# untitled.net
KiCad netlist of a schematic drawn in EAGLE
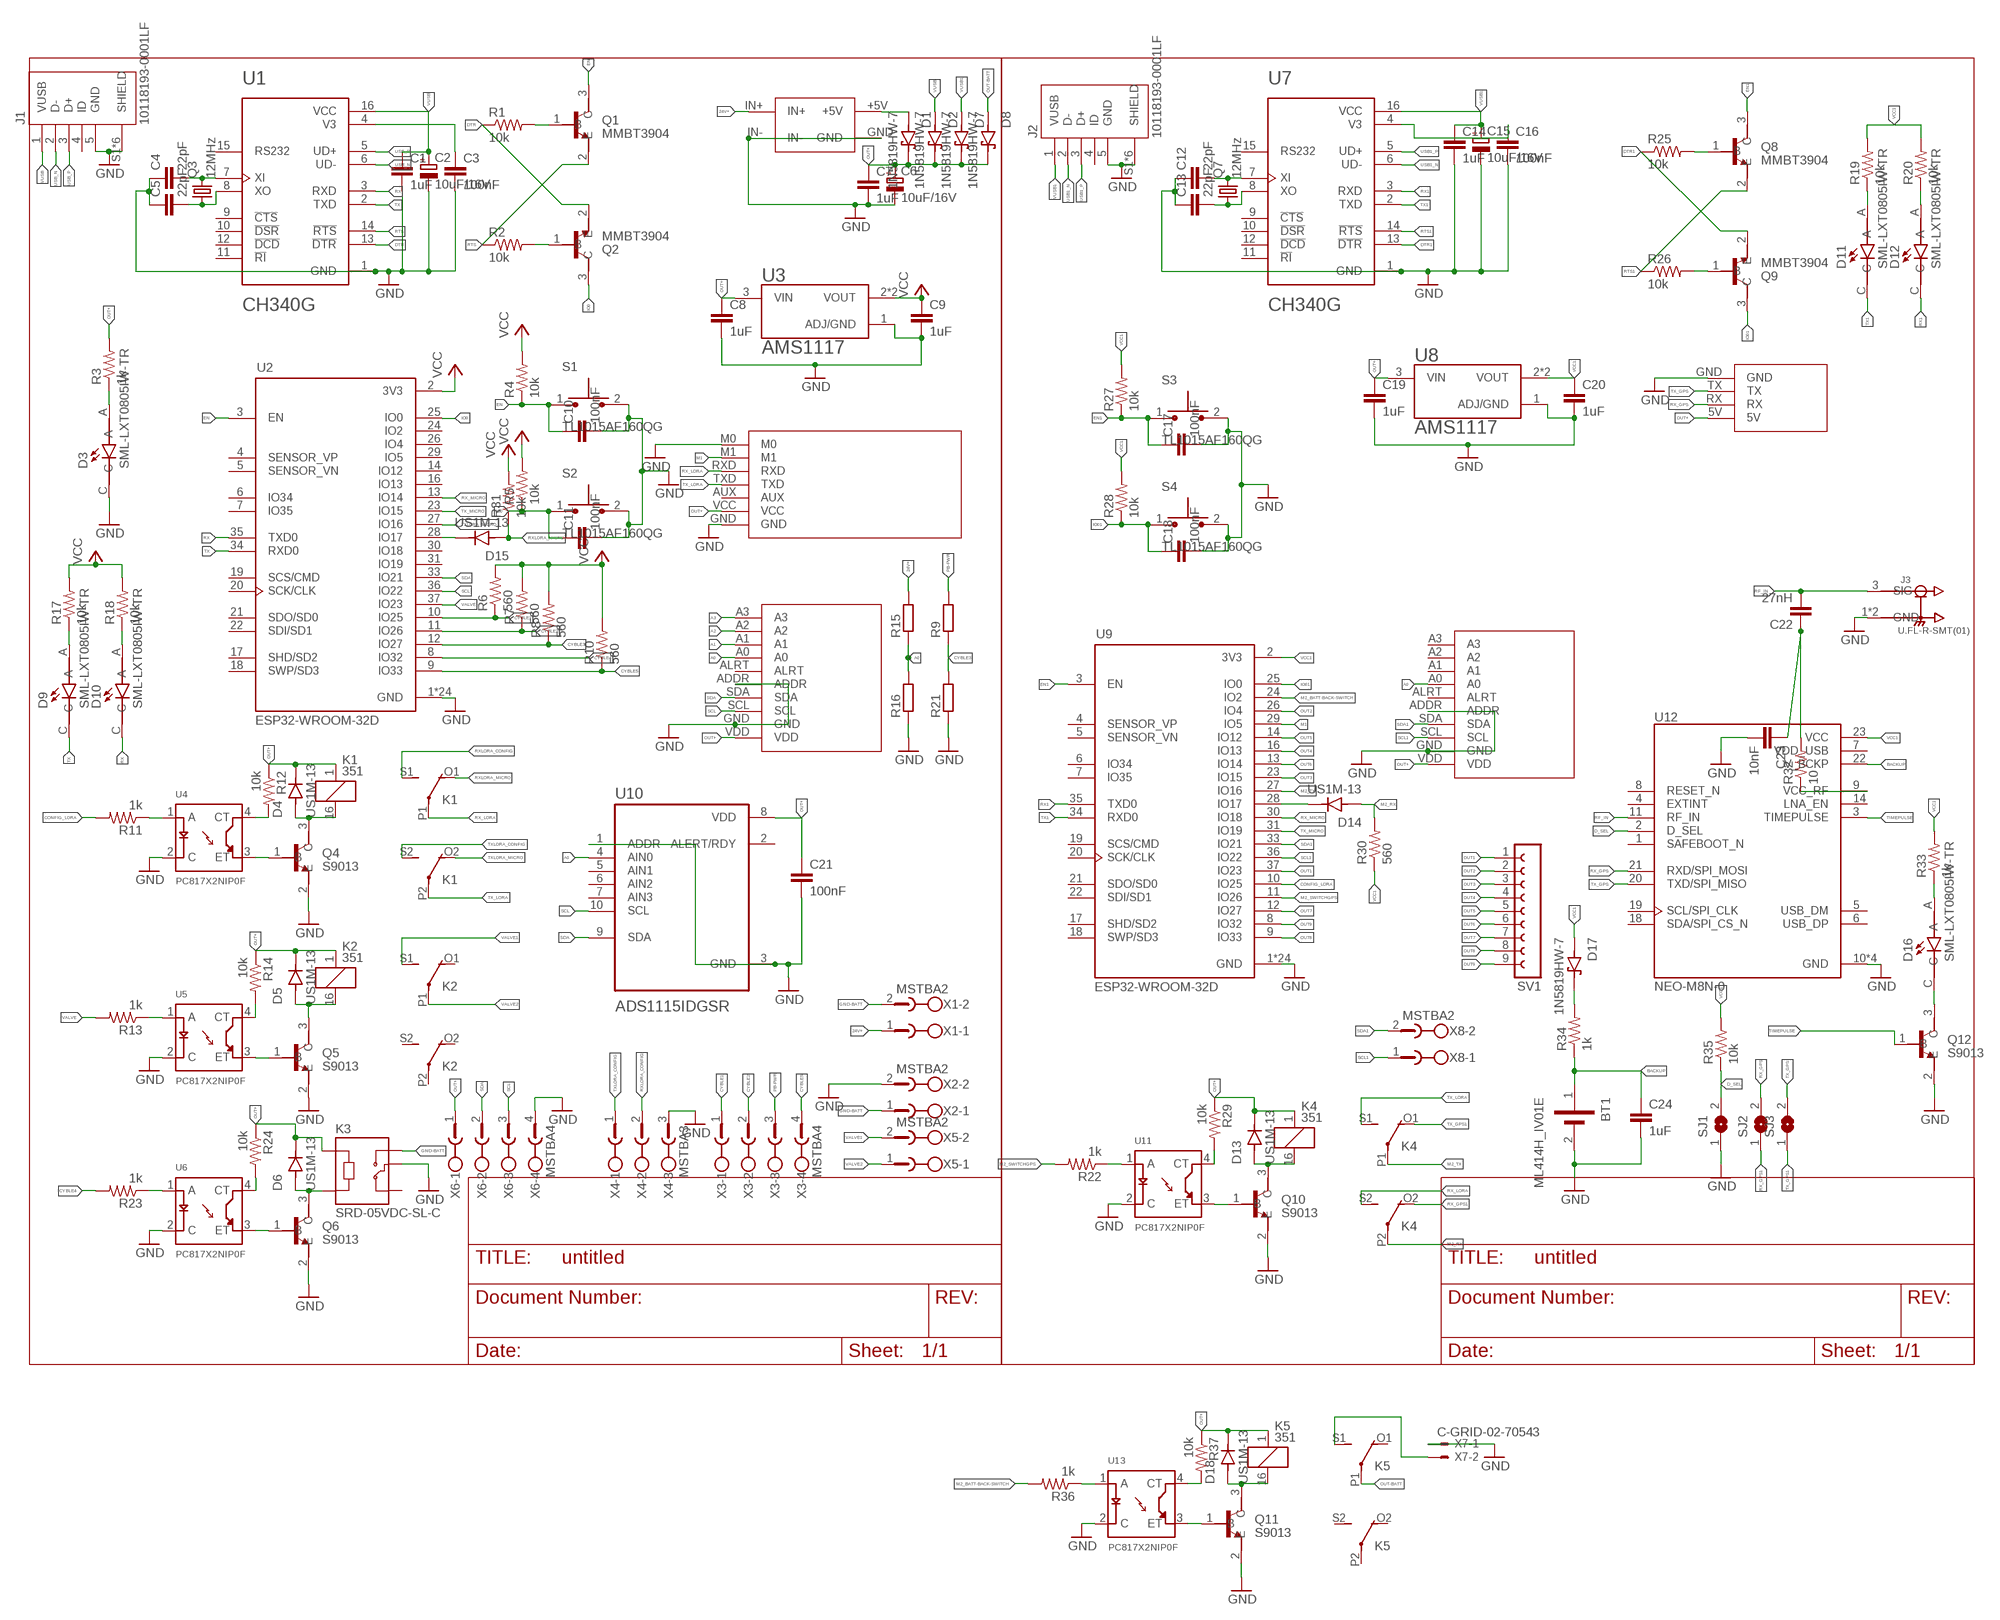
[diagram p0: schematic, sheet 1]

(export (version "E")
  (design (tool "Eeschema 10.0.6"))
  (components
    (comp (ref "ADS1")
      (value "ADS1115")
      (footprint "eagle-import:ADS1115")
      (libsource (lib "eagle-import") (part "ADS1115"))
    )
    (comp (ref "ADS2")
      (value "ADS1115")
      (footprint "eagle-import:ADS1115")
      (libsource (lib "eagle-import") (part "ADS1115"))
    )
    (comp (ref "BT1")
      (value "ML414H_IV01E")
      (footprint "eagle-import:SEIKO_ML414H_IV01E")
      (fields (field (name "MF") "Seiko Instruments") (field (name "MP") "ML414H IV01E"))
      (libsource (lib "eagle-import") (part "ML414H_IV01E"))
    )
    (comp (ref "C1")
      (value "1uF")
      (footprint "eagle-import:C0805K")
      (libsource (lib "eagle-import") (part "C-EUC0805K"))
    )
    (comp (ref "C2")
      (value "10uF/16V")
      (footprint "eagle-import:153CLV-0505")
      (libsource (lib "eagle-import") (part "CPOL-EU153CLV-0505"))
    )
    (comp (ref "C3")
      (value "100nF")
      (footprint "eagle-import:C0805K")
      (libsource (lib "eagle-import") (part "C-EUC0805K"))
    )
    (comp (ref "C4")
      (value "22pF")
      (footprint "eagle-import:C0805K")
      (libsource (lib "eagle-import") (part "C-EUC0805K"))
    )
    (comp (ref "C5")
      (value "22pF")
      (footprint "eagle-import:C0805K")
      (libsource (lib "eagle-import") (part "C-EUC0805K"))
    )
    (comp (ref "C6")
      (value "10uF/16V")
      (footprint "eagle-import:153CLV-0505")
      (libsource (lib "eagle-import") (part "CPOL-EU153CLV-0505"))
    )
    (comp (ref "C7")
      (value "1uF")
      (footprint "eagle-import:C0805K")
      (libsource (lib "eagle-import") (part "C-EUC0805K"))
    )
    (comp (ref "C8")
      (value "1uF")
      (footprint "eagle-import:C0805K")
      (libsource (lib "eagle-import") (part "C-EUC0805K"))
    )
    (comp (ref "C9")
      (value "1uF")
      (footprint "eagle-import:C0805K")
      (libsource (lib "eagle-import") (part "C-EUC0805K"))
    )
    (comp (ref "C10")
      (value "100nF")
      (footprint "eagle-import:C0805K")
      (libsource (lib "eagle-import") (part "C-EUC0805K"))
    )
    (comp (ref "C11")
      (value "100nF")
      (footprint "eagle-import:C0805K")
      (libsource (lib "eagle-import") (part "C-EUC0805K"))
    )
    (comp (ref "C12")
      (value "22pF")
      (footprint "eagle-import:C0805K")
      (libsource (lib "eagle-import") (part "C-EUC0805K"))
    )
    (comp (ref "C13")
      (value "22pF")
      (footprint "eagle-import:C0805K")
      (libsource (lib "eagle-import") (part "C-EUC0805K"))
    )
    (comp (ref "C14")
      (value "1uF")
      (footprint "eagle-import:C0805K")
      (libsource (lib "eagle-import") (part "C-EUC0805K"))
    )
    (comp (ref "C15")
      (value "10uF/16V")
      (footprint "eagle-import:153CLV-0505")
      (libsource (lib "eagle-import") (part "CPOL-EU153CLV-0505"))
    )
    (comp (ref "C16")
      (value "100nF")
      (footprint "eagle-import:C0805K")
      (libsource (lib "eagle-import") (part "C-EUC0805K"))
    )
    (comp (ref "C17")
      (value "100nF")
      (footprint "eagle-import:C0805K")
      (libsource (lib "eagle-import") (part "C-EUC0805K"))
    )
    (comp (ref "C18")
      (value "100nF")
      (footprint "eagle-import:C0805K")
      (libsource (lib "eagle-import") (part "C-EUC0805K"))
    )
    (comp (ref "C19")
      (value "1uF")
      (footprint "eagle-import:C0805K")
      (libsource (lib "eagle-import") (part "C-EUC0805K"))
    )
    (comp (ref "C20")
      (value "1uF")
      (footprint "eagle-import:C0805K")
      (libsource (lib "eagle-import") (part "C-EUC0805K"))
    )
    (comp (ref "C21")
      (value "100nF")
      (footprint "eagle-import:C0805K")
      (libsource (lib "eagle-import") (part "C-EUC0805K"))
    )
    (comp (ref "C22")
      (value "27nH")
      (footprint "eagle-import:C0805K")
      (libsource (lib "eagle-import") (part "C-EUC0805K"))
    )
    (comp (ref "C23")
      (value "10nF")
      (footprint "eagle-import:C0805K")
      (libsource (lib "eagle-import") (part "C-EUC0805K"))
    )
    (comp (ref "C24")
      (value "1uF")
      (footprint "eagle-import:C0805K")
      (libsource (lib "eagle-import") (part "C-EUC0805K"))
    )
    (comp (ref "D1")
      (value "1N5819HW-7")
      (footprint "eagle-import:SOD3715X145N")
      (fields (field (name "MF") "Diodes Inc."))
      (libsource (lib "eagle-import") (part "1N5819HW-7"))
    )
    (comp (ref "D2")
      (value "1N5819HW-7")
      (footprint "eagle-import:SOD3715X145N")
      (fields (field (name "MF") "Diodes Inc."))
      (libsource (lib "eagle-import") (part "1N5819HW-7"))
    )
    (comp (ref "D3")
      (value "SML-LXT0805IW-TR")
      (footprint "eagle-import:LEDC2012X120N")
      (fields (field (name "MF") "Lumex Opto/Components"))
      (libsource (lib "eagle-import") (part "SML-LXT0805IW-TR"))
    )
    (comp (ref "D4")
      (value "US1M-13")
      (footprint "eagle-import:DIOM5226X240N")
      (fields (field (name "MF") "Diodes Incorporated"))
      (libsource (lib "eagle-import") (part "US1M-13"))
    )
    (comp (ref "D5")
      (value "US1M-13")
      (footprint "eagle-import:DIOM5226X240N")
      (fields (field (name "MF") "Diodes Incorporated"))
      (libsource (lib "eagle-import") (part "US1M-13"))
    )
    (comp (ref "D6")
      (value "US1M-13")
      (footprint "eagle-import:DIOM5226X240N")
      (fields (field (name "MF") "Diodes Incorporated"))
      (libsource (lib "eagle-import") (part "US1M-13"))
    )
    (comp (ref "D7")
      (value "1N5819HW-7")
      (footprint "eagle-import:SOD3715X145N")
      (fields (field (name "MF") "Diodes Inc."))
      (libsource (lib "eagle-import") (part "1N5819HW-7"))
    )
    (comp (ref "D8")
      (value "1N5819HW-7")
      (footprint "eagle-import:SOD3715X145N")
      (fields (field (name "MF") "Diodes Inc."))
      (libsource (lib "eagle-import") (part "1N5819HW-7"))
    )
    (comp (ref "D9")
      (value "SML-LXT0805IW-TR")
      (footprint "eagle-import:LEDC2012X120N")
      (fields (field (name "MF") "Lumex Opto/Components"))
      (libsource (lib "eagle-import") (part "SML-LXT0805IW-TR"))
    )
    (comp (ref "D10")
      (value "SML-LXT0805IW-TR")
      (footprint "eagle-import:LEDC2012X120N")
      (fields (field (name "MF") "Lumex Opto/Components"))
      (libsource (lib "eagle-import") (part "SML-LXT0805IW-TR"))
    )
    (comp (ref "D11")
      (value "SML-LXT0805IW-TR")
      (footprint "eagle-import:LEDC2012X120N")
      (fields (field (name "MF") "Lumex Opto/Components"))
      (libsource (lib "eagle-import") (part "SML-LXT0805IW-TR"))
    )
    (comp (ref "D12")
      (value "SML-LXT0805IW-TR")
      (footprint "eagle-import:LEDC2012X120N")
      (fields (field (name "MF") "Lumex Opto/Components"))
      (libsource (lib "eagle-import") (part "SML-LXT0805IW-TR"))
    )
    (comp (ref "D13")
      (value "US1M-13")
      (footprint "eagle-import:DIOM5226X240N")
      (fields (field (name "MF") "Diodes Incorporated"))
      (libsource (lib "eagle-import") (part "US1M-13"))
    )
    (comp (ref "D14")
      (value "US1M-13")
      (footprint "eagle-import:DIOM5226X240N")
      (fields (field (name "MF") "Diodes Incorporated"))
      (libsource (lib "eagle-import") (part "US1M-13"))
    )
    (comp (ref "D15")
      (value "US1M-13")
      (footprint "eagle-import:DIOM5226X240N")
      (fields (field (name "MF") "Diodes Incorporated"))
      (libsource (lib "eagle-import") (part "US1M-13"))
    )
    (comp (ref "D16")
      (value "SML-LXT0805IW-TR")
      (footprint "eagle-import:LEDC2012X120N")
      (fields (field (name "MF") "Lumex Opto/Components"))
      (libsource (lib "eagle-import") (part "SML-LXT0805IW-TR"))
    )
    (comp (ref "D17")
      (value "1N5819HW-7")
      (footprint "eagle-import:SOD3715X145N")
      (fields (field (name "MF") "Diodes Inc."))
      (libsource (lib "eagle-import") (part "1N5819HW-7"))
    )
    (comp (ref "D18")
      (value "US1M-13")
      (footprint "eagle-import:DIOM5226X240N")
      (fields (field (name "MF") "Diodes Incorporated"))
      (libsource (lib "eagle-import") (part "US1M-13"))
    )
    (comp (ref "EBYTEE220-900T22D1")
      (value "EBYTEE220-900T22D")
      (footprint "eagle-import:EBYTEE220-900T22D")
      (libsource (lib "eagle-import") (part "EBYTEE220-900T22D"))
    )
    (comp (ref "J1")
      (value "10118193-0001LF")
      (footprint "eagle-import:FCI_10118193-0001LF")
      (fields (field (name "MF") "FCI"))
      (libsource (lib "eagle-import") (part "10118193-0001LF"))
    )
    (comp (ref "J2")
      (value "10118193-0001LF")
      (footprint "eagle-import:FCI_10118193-0001LF")
      (fields (field (name "MF") "FCI"))
      (libsource (lib "eagle-import") (part "10118193-0001LF"))
    )
    (comp (ref "J3")
      (value "U.FL-R-SMT(01)")
      (footprint "eagle-import:HRS_U.FL-R-SMT(01)")
      (fields (field (name "MF") "Hirose"))
      (libsource (lib "eagle-import") (part "U.FL-R-SMT(01)"))
    )
    (comp (ref "K1")
      (value "351")
      (footprint "eagle-import:351")
      (libsource (lib "eagle-import") (part "351"))
    )
    (comp (ref "K2")
      (value "351")
      (footprint "eagle-import:351")
      (libsource (lib "eagle-import") (part "351"))
    )
    (comp (ref "K3")
      (value "SRD-05VDC-SL-C")
      (footprint "eagle-import:RELAY_SRD-05VDC-SL-C")
      (fields (field (name "MF") "Songle Relay"))
      (libsource (lib "eagle-import") (part "SRD-05VDC-SL-C"))
    )
    (comp (ref "K4")
      (value "351")
      (footprint "eagle-import:351")
      (libsource (lib "eagle-import") (part "351"))
    )
    (comp (ref "K5")
      (value "351")
      (footprint "eagle-import:351")
      (libsource (lib "eagle-import") (part "351"))
    )
    (comp (ref "NEO-6MGPS1")
      (value "NEO-6MGPS")
      (footprint "eagle-import:NEO-6MGPS")
      (libsource (lib "eagle-import") (part "NEO-6MGPS"))
    )
    (comp (ref "Q1")
      (value "MMBT3904")
      (footprint "eagle-import:SOT95P240X120-3N")
      (fields (field (name "MF") "ON Semiconductor"))
      (libsource (lib "eagle-import") (part "MMBT3904"))
    )
    (comp (ref "Q2")
      (value "MMBT3904")
      (footprint "eagle-import:SOT95P240X120-3N")
      (fields (field (name "MF") "ON Semiconductor"))
      (libsource (lib "eagle-import") (part "MMBT3904"))
    )
    (comp (ref "Q3")
      (value "12MHz")
      (footprint "eagle-import:SM49")
      (libsource (lib "eagle-import") (part "CRYSTALSM49"))
    )
    (comp (ref "Q4")
      (value "S9013")
      (footprint "eagle-import:SOT95P240X120-3N")
      (fields (field (name "MF") "JCET"))
      (libsource (lib "eagle-import") (part "S9013"))
    )
    (comp (ref "Q5")
      (value "S9013")
      (footprint "eagle-import:SOT95P240X120-3N")
      (fields (field (name "MF") "JCET"))
      (libsource (lib "eagle-import") (part "S9013"))
    )
    (comp (ref "Q6")
      (value "S9013")
      (footprint "eagle-import:SOT95P240X120-3N")
      (fields (field (name "MF") "JCET"))
      (libsource (lib "eagle-import") (part "S9013"))
    )
    (comp (ref "Q7")
      (value "12MHz")
      (footprint "eagle-import:SM49")
      (libsource (lib "eagle-import") (part "CRYSTALSM49"))
    )
    (comp (ref "Q8")
      (value "MMBT3904")
      (footprint "eagle-import:SOT95P240X120-3N")
      (fields (field (name "MF") "ON Semiconductor"))
      (libsource (lib "eagle-import") (part "MMBT3904"))
    )
    (comp (ref "Q9")
      (value "MMBT3904")
      (footprint "eagle-import:SOT95P240X120-3N")
      (fields (field (name "MF") "ON Semiconductor"))
      (libsource (lib "eagle-import") (part "MMBT3904"))
    )
    (comp (ref "Q10")
      (value "S9013")
      (footprint "eagle-import:SOT95P240X120-3N")
      (fields (field (name "MF") "JCET"))
      (libsource (lib "eagle-import") (part "S9013"))
    )
    (comp (ref "Q11")
      (value "S9013")
      (footprint "eagle-import:SOT95P240X120-3N")
      (fields (field (name "MF") "JCET"))
      (libsource (lib "eagle-import") (part "S9013"))
    )
    (comp (ref "Q12")
      (value "S9013")
      (footprint "eagle-import:SOT95P240X120-3N")
      (fields (field (name "MF") "JCET"))
      (libsource (lib "eagle-import") (part "S9013"))
    )
    (comp (ref "R1")
      (value "10k")
      (footprint "eagle-import:M0805")
      (libsource (lib "eagle-import") (part "R-US_M0805"))
    )
    (comp (ref "R2")
      (value "10k")
      (footprint "eagle-import:M0805")
      (libsource (lib "eagle-import") (part "R-US_M0805"))
    )
    (comp (ref "R3")
      (value "1k")
      (footprint "eagle-import:M0805")
      (libsource (lib "eagle-import") (part "R-US_M0805"))
    )
    (comp (ref "R4")
      (value "10k")
      (footprint "eagle-import:M0805")
      (libsource (lib "eagle-import") (part "R-US_M0805"))
    )
    (comp (ref "R5")
      (value "10k")
      (footprint "eagle-import:M0805")
      (libsource (lib "eagle-import") (part "R-US_M0805"))
    )
    (comp (ref "R6")
      (value "560")
      (footprint "eagle-import:M0805")
      (libsource (lib "eagle-import") (part "R-US_M0805"))
    )
    (comp (ref "R7")
      (value "560")
      (footprint "eagle-import:M0805")
      (libsource (lib "eagle-import") (part "R-US_M0805"))
    )
    (comp (ref "R8")
      (value "560")
      (footprint "eagle-import:M0805")
      (libsource (lib "eagle-import") (part "R-US_M0805"))
    )
    (comp (ref "R9")
      (value "R-EU_0207/12")
      (footprint "eagle-import:0207_12")
      (libsource (lib "eagle-import") (part "R-EU_0207/12"))
    )
    (comp (ref "R10")
      (value "560")
      (footprint "eagle-import:M0805")
      (libsource (lib "eagle-import") (part "R-US_M0805"))
    )
    (comp (ref "R11")
      (value "1k")
      (footprint "eagle-import:M0805")
      (libsource (lib "eagle-import") (part "R-US_M0805"))
    )
    (comp (ref "R12")
      (value "10k")
      (footprint "eagle-import:M0805")
      (libsource (lib "eagle-import") (part "R-US_M0805"))
    )
    (comp (ref "R13")
      (value "1k")
      (footprint "eagle-import:M0805")
      (libsource (lib "eagle-import") (part "R-US_M0805"))
    )
    (comp (ref "R14")
      (value "10k")
      (footprint "eagle-import:M0805")
      (libsource (lib "eagle-import") (part "R-US_M0805"))
    )
    (comp (ref "R15")
      (value "R-EU_0207/12")
      (footprint "eagle-import:0207_12")
      (libsource (lib "eagle-import") (part "R-EU_0207/12"))
    )
    (comp (ref "R16")
      (value "R-EU_0207/12")
      (footprint "eagle-import:0207_12")
      (libsource (lib "eagle-import") (part "R-EU_0207/12"))
    )
    (comp (ref "R17")
      (value "10k")
      (footprint "eagle-import:M0805")
      (libsource (lib "eagle-import") (part "R-US_M0805"))
    )
    (comp (ref "R18")
      (value "10k")
      (footprint "eagle-import:M0805")
      (libsource (lib "eagle-import") (part "R-US_M0805"))
    )
    (comp (ref "R19")
      (value "10k")
      (footprint "eagle-import:M0805")
      (libsource (lib "eagle-import") (part "R-US_M0805"))
    )
    (comp (ref "R20")
      (value "10k")
      (footprint "eagle-import:M0805")
      (libsource (lib "eagle-import") (part "R-US_M0805"))
    )
    (comp (ref "R21")
      (value "R-EU_0207/12")
      (footprint "eagle-import:0207_12")
      (libsource (lib "eagle-import") (part "R-EU_0207/12"))
    )
    (comp (ref "R22")
      (value "1k")
      (footprint "eagle-import:M0805")
      (libsource (lib "eagle-import") (part "R-US_M0805"))
    )
    (comp (ref "R23")
      (value "1k")
      (footprint "eagle-import:M0805")
      (libsource (lib "eagle-import") (part "R-US_M0805"))
    )
    (comp (ref "R24")
      (value "10k")
      (footprint "eagle-import:M0805")
      (libsource (lib "eagle-import") (part "R-US_M0805"))
    )
    (comp (ref "R25")
      (value "10k")
      (footprint "eagle-import:M0805")
      (libsource (lib "eagle-import") (part "R-US_M0805"))
    )
    (comp (ref "R26")
      (value "10k")
      (footprint "eagle-import:M0805")
      (libsource (lib "eagle-import") (part "R-US_M0805"))
    )
    (comp (ref "R27")
      (value "10k")
      (footprint "eagle-import:M0805")
      (libsource (lib "eagle-import") (part "R-US_M0805"))
    )
    (comp (ref "R28")
      (value "10k")
      (footprint "eagle-import:M0805")
      (libsource (lib "eagle-import") (part "R-US_M0805"))
    )
    (comp (ref "R29")
      (value "10k")
      (footprint "eagle-import:M0805")
      (libsource (lib "eagle-import") (part "R-US_M0805"))
    )
    (comp (ref "R30")
      (value "560")
      (footprint "eagle-import:M0805")
      (libsource (lib "eagle-import") (part "R-US_M0805"))
    )
    (comp (ref "R31")
      (value "10k")
      (footprint "eagle-import:M0805")
      (libsource (lib "eagle-import") (part "R-US_M0805"))
    )
    (comp (ref "R32")
      (value "10")
      (footprint "eagle-import:M0805")
      (libsource (lib "eagle-import") (part "R-US_M0805"))
    )
    (comp (ref "R33")
      (value "1k")
      (footprint "eagle-import:M0805")
      (libsource (lib "eagle-import") (part "R-US_M0805"))
    )
    (comp (ref "R34")
      (value "1k")
      (footprint "eagle-import:M0805")
      (libsource (lib "eagle-import") (part "R-US_M0805"))
    )
    (comp (ref "R35")
      (value "10k")
      (footprint "eagle-import:M0805")
      (libsource (lib "eagle-import") (part "R-US_M0805"))
    )
    (comp (ref "R36")
      (value "1k")
      (footprint "eagle-import:M0805")
      (libsource (lib "eagle-import") (part "R-US_M0805"))
    )
    (comp (ref "R37")
      (value "10k")
      (footprint "eagle-import:M0805")
      (libsource (lib "eagle-import") (part "R-US_M0805"))
    )
    (comp (ref "S1")
      (value "TL1015AF160QG")
      (footprint "eagle-import:SW_TL1015AF160QG")
      (fields (field (name "MF") "E-Switch"))
      (libsource (lib "eagle-import") (part "TL1015AF160QG"))
    )
    (comp (ref "S2")
      (value "TL1015AF160QG")
      (footprint "eagle-import:SW_TL1015AF160QG")
      (fields (field (name "MF") "E-Switch"))
      (libsource (lib "eagle-import") (part "TL1015AF160QG"))
    )
    (comp (ref "S3")
      (value "TL1015AF160QG")
      (footprint "eagle-import:SW_TL1015AF160QG")
      (fields (field (name "MF") "E-Switch"))
      (libsource (lib "eagle-import") (part "TL1015AF160QG"))
    )
    (comp (ref "S4")
      (value "TL1015AF160QG")
      (footprint "eagle-import:SW_TL1015AF160QG")
      (fields (field (name "MF") "E-Switch"))
      (libsource (lib "eagle-import") (part "TL1015AF160QG"))
    )
    (comp (ref "SJ1") (value "SJ") (footprint "eagle-import:SJ") (libsource (lib "eagle-import") (part "SJ")))
    (comp (ref "SJ2") (value "SJ") (footprint "eagle-import:SJ") (libsource (lib "eagle-import") (part "SJ")))
    (comp (ref "SJ3") (value "SJ") (footprint "eagle-import:SJ") (libsource (lib "eagle-import") (part "SJ")))
    (comp (ref "SUPER-STEPDOWN1")
      (value "SUPER-STEPDOWN")
      (footprint "eagle-import:SUPER-STEPDOWN")
      (libsource (lib "eagle-import") (part "SUPER-STEPDOWN"))
    )
    (comp (ref "SV1")
      (value "FE09-1")
      (footprint "eagle-import:FE09")
      (libsource (lib "eagle-import") (part "FE09-1"))
    )
    (comp (ref "U1")
      (value "CH340G")
      (footprint "eagle-import:SOIC127P600X180-16N")
      (fields (field (name "MF") "WCH") (field (name "MP") "Ch340G"))
      (libsource (lib "eagle-import") (part "CH340G"))
    )
    (comp (ref "U2")
      (value "ESP32-WROOM-32D")
      (footprint "eagle-import:MODULE_ESP32-WROOM-32D")
      (fields (field (name "MF") "Espressif Systems"))
      (libsource (lib "eagle-import") (part "ESP32-WROOM-32D"))
    )
    (comp (ref "U3")
      (value "AMS1117")
      (footprint "eagle-import:SOT229P700X180-4N")
      (fields (field (name "MF") "Advanced Monolithic Systems"))
      (libsource (lib "eagle-import") (part "AMS1117"))
    )
    (comp (ref "U4")
      (value "PC817X2NIP0F")
      (footprint "eagle-import:SOT254P975X400-4N")
      (fields (field (name "MF") "Sharp Microelectronics"))
      (libsource (lib "eagle-import") (part "PC817X2NIP0F"))
    )
    (comp (ref "U5")
      (value "PC817X2NIP0F")
      (footprint "eagle-import:SOT254P975X400-4N")
      (fields (field (name "MF") "Sharp Microelectronics"))
      (libsource (lib "eagle-import") (part "PC817X2NIP0F"))
    )
    (comp (ref "U6")
      (value "PC817X2NIP0F")
      (footprint "eagle-import:SOT254P975X400-4N")
      (fields (field (name "MF") "Sharp Microelectronics"))
      (libsource (lib "eagle-import") (part "PC817X2NIP0F"))
    )
    (comp (ref "U7")
      (value "CH340G")
      (footprint "eagle-import:SOIC127P600X180-16N")
      (fields (field (name "MF") "WCH") (field (name "MP") "Ch340G"))
      (libsource (lib "eagle-import") (part "CH340G"))
    )
    (comp (ref "U8")
      (value "AMS1117")
      (footprint "eagle-import:SOT229P700X180-4N")
      (fields (field (name "MF") "Advanced Monolithic Systems"))
      (libsource (lib "eagle-import") (part "AMS1117"))
    )
    (comp (ref "U9")
      (value "ESP32-WROOM-32D")
      (footprint "eagle-import:MODULE_ESP32-WROOM-32D")
      (fields (field (name "MF") "Espressif Systems"))
      (libsource (lib "eagle-import") (part "ESP32-WROOM-32D"))
    )
    (comp (ref "U10")
      (value "ADS1115IDGSR")
      (footprint "eagle-import:SOP50P490X110-10N")
      (fields (field (name "MF") "Texas Instruments"))
      (libsource (lib "eagle-import") (part "ADS1115IDGSR"))
    )
    (comp (ref "U11")
      (value "PC817X2NIP0F")
      (footprint "eagle-import:SOT254P975X400-4N")
      (fields (field (name "MF") "Sharp Microelectronics"))
      (libsource (lib "eagle-import") (part "PC817X2NIP0F"))
    )
    (comp (ref "U12")
      (value "NEO-M8N-0")
      (footprint "eagle-import:XCVR_NEO-M8N-0")
      (fields (field (name "MF") "U-Blox America"))
      (libsource (lib "eagle-import") (part "NEO-M8N-0"))
    )
    (comp (ref "U13")
      (value "PC817X2NIP0F")
      (footprint "eagle-import:SOT254P975X400-4N")
      (fields (field (name "MF") "Sharp Microelectronics"))
      (libsource (lib "eagle-import") (part "PC817X2NIP0F"))
    )
    (comp (ref "X1")
      (value "MSTBA2")
      (footprint "eagle-import:MSTBA2")
      (fields (field (name "MF") "FARNELL") (field (name "MPN") "1757242"))
      (libsource (lib "eagle-import") (part "MSTBA2"))
    )
    (comp (ref "X2")
      (value "MSTBA2")
      (footprint "eagle-import:MSTBA2")
      (fields (field (name "MF") "FARNELL") (field (name "MPN") "1757242"))
      (libsource (lib "eagle-import") (part "MSTBA2"))
    )
    (comp (ref "X3")
      (value "MSTBA4")
      (footprint "eagle-import:MSTBA4")
      (fields (field (name "MF") "FARNELL") (field (name "MPN") "1757268"))
      (libsource (lib "eagle-import") (part "MSTBA4"))
    )
    (comp (ref "X4")
      (value "MSTBA3")
      (footprint "eagle-import:MSTBA3")
      (fields (field (name "MF") "FARNELL") (field (name "MPN") "1757255"))
      (libsource (lib "eagle-import") (part "MSTBA3"))
    )
    (comp (ref "X5")
      (value "MSTBA2")
      (footprint "eagle-import:MSTBA2")
      (fields (field (name "MF") "FARNELL") (field (name "MPN") "1757242"))
      (libsource (lib "eagle-import") (part "MSTBA2"))
    )
    (comp (ref "X6")
      (value "MSTBA4")
      (footprint "eagle-import:MSTBA4")
      (fields (field (name "MF") "FARNELL") (field (name "MPN") "1757268"))
      (libsource (lib "eagle-import") (part "MSTBA4"))
    )
    (comp (ref "X7")
      (value "C-GRID-02-70543")
      (footprint "eagle-import:70543-02")
      (fields (field (name "MF") "MOLEX"))
      (libsource (lib "eagle-import") (part "C-GRID-02-70543"))
    )
    (comp (ref "X8")
      (value "MSTBA2")
      (footprint "eagle-import:MSTBA2")
      (fields (field (name "MF") "FARNELL") (field (name "MPN") "1757242"))
      (libsource (lib "eagle-import") (part "MSTBA2"))
    )
  )
  (nets
    (net (code "1") (name "/VDD_USB") (class "Default")
      (node (ref "U12") (pin "7") (pinfunction "VDD_USB_7") (pintype "power_in"))
    )
    (net (code "2") (name "24V+") (class "Default")
      (node (ref "R15") (pin "2") (pinfunction "2_2") (pintype "passive"))
      (node (ref "SUPER-STEPDOWN1") (pin "IN+") (pinfunction "IN+_IN+") (pintype "bidirectional"))
      (node (ref "X1") (pin "1") (pinfunction "1_1") (pintype "passive"))
    )
    (net (code "3") (name "A0") (class "Default")
      (node (ref "ADS1") (pin "A0") (pinfunction "A0_A0") (pintype "bidirectional"))
      (node (ref "ADS2") (pin "A0") (pinfunction "A0_A0") (pintype "bidirectional"))
      (node (ref "R15") (pin "1") (pinfunction "1_1") (pintype "passive"))
      (node (ref "R16") (pin "2") (pinfunction "2_2") (pintype "passive"))
      (node (ref "U10") (pin "4") (pinfunction "AIN0_4") (pintype "input"))
    )
    (net (code "4") (name "A1") (class "Default")
      (node (ref "ADS1") (pin "A1") (pinfunction "A1_A1") (pintype "bidirectional"))
    )
    (net (code "5") (name "A2") (class "Default")
      (node (ref "ADS1") (pin "A2") (pinfunction "A2_A2") (pintype "bidirectional"))
    )
    (net (code "6") (name "A3") (class "Default")
      (node (ref "ADS1") (pin "A3") (pinfunction "A3_A3") (pintype "bidirectional"))
    )
    (net (code "7") (name "BACKUP") (class "Default")
      (node (ref "BT1") (pin "1") (pinfunction "POS_1") (pintype "passive"))
      (node (ref "C24") (pin "1") (pinfunction "1_1") (pintype "passive"))
      (node (ref "R34") (pin "1") (pinfunction "1_1") (pintype "passive"))
      (node (ref "U12") (pin "22") (pinfunction "V_BCKP_22") (pintype "power_in"))
    )
    (net (code "8") (name "CONFIG_LORA") (class "Default")
      (node (ref "R11") (pin "2") (pinfunction "2_2") (pintype "passive"))
      (node (ref "U9") (pin "10") (pinfunction "IO25_10") (pintype "bidirectional"))
    )
    (net (code "9") (name "CYBLE1") (class "Default")
      (node (ref "R6") (pin "1") (pinfunction "1_1") (pintype "passive"))
      (node (ref "U2") (pin "10") (pinfunction "IO25_10") (pintype "bidirectional"))
      (node (ref "X3") (pin "1") (pinfunction "1_1") (pintype "passive"))
    )
    (net (code "10") (name "CYBLE2") (class "Default")
      (node (ref "R7") (pin "1") (pinfunction "1_1") (pintype "passive"))
      (node (ref "U2") (pin "11") (pinfunction "IO26_11") (pintype "bidirectional"))
      (node (ref "X3") (pin "2") (pinfunction "1_2") (pintype "passive"))
    )
    (net (code "11") (name "CYBLE3") (class "Default")
      (node (ref "R21") (pin "2") (pinfunction "2_2") (pintype "passive"))
      (node (ref "R8") (pin "1") (pinfunction "1_1") (pintype "passive"))
      (node (ref "R9") (pin "1") (pinfunction "1_1") (pintype "passive"))
      (node (ref "U2") (pin "12") (pinfunction "IO27_12") (pintype "bidirectional"))
    )
    (net (code "12") (name "CYBLE4") (class "Default")
      (node (ref "R23") (pin "2") (pinfunction "2_2") (pintype "passive"))
      (node (ref "U2") (pin "8") (pinfunction "IO32_8") (pintype "bidirectional"))
    )
    (net (code "13") (name "CYBLE5") (class "Default")
      (node (ref "R10") (pin "1") (pinfunction "1_1") (pintype "passive"))
      (node (ref "U2") (pin "9") (pinfunction "IO33_9") (pintype "bidirectional"))
      (node (ref "X3") (pin "4") (pinfunction "1_4") (pintype "passive"))
    )
    (net (code "14") (name "DTR") (class "Default")
      (node (ref "Q2") (pin "2") (pinfunction "E_2") (pintype "passive"))
      (node (ref "R1") (pin "1") (pinfunction "1_1") (pintype "passive"))
      (node (ref "U1") (pin "13") (pinfunction "~{DTR}_13") (pintype "output"))
    )
    (net (code "15") (name "DTR1") (class "Default")
      (node (ref "Q9") (pin "2") (pinfunction "E_2") (pintype "passive"))
      (node (ref "R25") (pin "1") (pinfunction "1_1") (pintype "passive"))
      (node (ref "U7") (pin "13") (pinfunction "~{DTR}_13") (pintype "output"))
    )
    (net (code "16") (name "D_SEL") (class "Default")
      (node (ref "R35") (pin "1") (pinfunction "1_1") (pintype "passive"))
      (node (ref "SJ1") (pin "2") (pinfunction "2_2") (pintype "passive"))
      (node (ref "U12") (pin "2") (pinfunction "D_SEL_2") (pintype "input"))
    )
    (net (code "17") (name "EN") (class "Default")
      (node (ref "C10") (pin "1") (pinfunction "1_1") (pintype "passive"))
      (node (ref "Q1") (pin "3") (pinfunction "C_3") (pintype "passive"))
      (node (ref "R4") (pin "1") (pinfunction "1_1") (pintype "passive"))
      (node (ref "S1") (pin "1") (pinfunction "1_1") (pintype "passive"))
      (node (ref "U2") (pin "3") (pinfunction "EN_3") (pintype "input"))
    )
    (net (code "18") (name "EN1") (class "Default")
      (node (ref "C17") (pin "1") (pinfunction "1_1") (pintype "passive"))
      (node (ref "Q8") (pin "3") (pinfunction "C_3") (pintype "passive"))
      (node (ref "R27") (pin "1") (pinfunction "1_1") (pintype "passive"))
      (node (ref "S3") (pin "1") (pinfunction "1_1") (pintype "passive"))
      (node (ref "U9") (pin "3") (pinfunction "EN_3") (pintype "input"))
    )
    (net (code "19") (name "GND") (class "Default")
      (node (ref "ADS1") (pin "ADDR") (pinfunction "ADDR_ADDR") (pintype "bidirectional"))
      (node (ref "ADS1") (pin "GND") (pinfunction "GND_GND") (pintype "bidirectional"))
      (node (ref "ADS2") (pin "ADDR") (pinfunction "ADDR_ADDR") (pintype "bidirectional"))
      (node (ref "ADS2") (pin "GND") (pinfunction "GND_GND") (pintype "bidirectional"))
      (node (ref "BT1") (pin "2") (pinfunction "NEG_2") (pintype "passive"))
      (node (ref "C1") (pin "2") (pinfunction "2_2") (pintype "passive"))
      (node (ref "C10") (pin "2") (pinfunction "2_2") (pintype "passive"))
      (node (ref "C11") (pin "2") (pinfunction "2_2") (pintype "passive"))
      (node (ref "C12") (pin "1") (pinfunction "1_1") (pintype "passive"))
      (node (ref "C13") (pin "1") (pinfunction "1_1") (pintype "passive"))
      (node (ref "C14") (pin "2") (pinfunction "2_2") (pintype "passive"))
      (node (ref "C15") (pin "-") (pinfunction "-_-") (pintype "passive"))
      (node (ref "C16") (pin "2") (pinfunction "2_2") (pintype "passive"))
      (node (ref "C17") (pin "2") (pinfunction "2_2") (pintype "passive"))
      (node (ref "C18") (pin "2") (pinfunction "2_2") (pintype "passive"))
      (node (ref "C19") (pin "2") (pinfunction "2_2") (pintype "passive"))
      (node (ref "C2") (pin "-") (pinfunction "-_-") (pintype "passive"))
      (node (ref "C20") (pin "2") (pinfunction "2_2") (pintype "passive"))
      (node (ref "C21") (pin "2") (pinfunction "2_2") (pintype "passive"))
      (node (ref "C23") (pin "2") (pinfunction "2_2") (pintype "passive"))
      (node (ref "C24") (pin "2") (pinfunction "2_2") (pintype "passive"))
      (node (ref "C3") (pin "2") (pinfunction "2_2") (pintype "passive"))
      (node (ref "C4") (pin "1") (pinfunction "1_1") (pintype "passive"))
      (node (ref "C5") (pin "1") (pinfunction "1_1") (pintype "passive"))
      (node (ref "C6") (pin "-") (pinfunction "-_-") (pintype "passive"))
      (node (ref "C7") (pin "2") (pinfunction "2_2") (pintype "passive"))
      (node (ref "C8") (pin "2") (pinfunction "2_2") (pintype "passive"))
      (node (ref "C9") (pin "2") (pinfunction "2_2") (pintype "passive"))
      (node (ref "D3") (pin "C") (pinfunction "C_C") (pintype "passive"))
      (node (ref "EBYTEE220-900T22D1") (pin "GND") (pinfunction "GND_GND") (pintype "bidirectional"))
      (node (ref "EBYTEE220-900T22D1") (pin "M0") (pinfunction "M0_M0") (pintype "bidirectional"))
      (node (ref "J1") (pin "5") (pinfunction "GND_5") (pintype "passive"))
      (node (ref "J1") (pin "S1") (pinfunction "SHIELD_S1") (pintype "passive"))
      (node (ref "J1") (pin "S2") (pinfunction "SHIELD_S2") (pintype "passive"))
      (node (ref "J1") (pin "S3") (pinfunction "SHIELD_S3") (pintype "passive"))
      (node (ref "J1") (pin "S4") (pinfunction "SHIELD_S4") (pintype "passive"))
      (node (ref "J1") (pin "S5") (pinfunction "SHIELD_S5") (pintype "passive"))
      (node (ref "J1") (pin "S6") (pinfunction "SHIELD_S6") (pintype "passive"))
      (node (ref "J2") (pin "5") (pinfunction "GND_5") (pintype "passive"))
      (node (ref "J2") (pin "S1") (pinfunction "SHIELD_S1") (pintype "passive"))
      (node (ref "J2") (pin "S2") (pinfunction "SHIELD_S2") (pintype "passive"))
      (node (ref "J2") (pin "S3") (pinfunction "SHIELD_S3") (pintype "passive"))
      (node (ref "J2") (pin "S4") (pinfunction "SHIELD_S4") (pintype "passive"))
      (node (ref "J2") (pin "S5") (pinfunction "SHIELD_S5") (pintype "passive"))
      (node (ref "J2") (pin "S6") (pinfunction "SHIELD_S6") (pintype "passive"))
      (node (ref "J3") (pin "1") (pinfunction "GND_1") (pintype "passive"))
      (node (ref "J3") (pin "2") (pinfunction "GND_2") (pintype "passive"))
      (node (ref "K3") (pin "COM") (pinfunction "COM_COM") (pintype "passive"))
      (node (ref "NEO-6MGPS1") (pin "GND") (pinfunction "GND_GND") (pintype "bidirectional"))
      (node (ref "Q10") (pin "2") (pinfunction "E_2") (pintype "passive"))
      (node (ref "Q11") (pin "2") (pinfunction "E_2") (pintype "passive"))
      (node (ref "Q12") (pin "2") (pinfunction "E_2") (pintype "passive"))
      (node (ref "Q4") (pin "2") (pinfunction "E_2") (pintype "passive"))
      (node (ref "Q5") (pin "2") (pinfunction "E_2") (pintype "passive"))
      (node (ref "Q6") (pin "2") (pinfunction "E_2") (pintype "passive"))
      (node (ref "R16") (pin "1") (pinfunction "1_1") (pintype "passive"))
      (node (ref "R21") (pin "1") (pinfunction "1_1") (pintype "passive"))
      (node (ref "S1") (pin "2") (pinfunction "2_2") (pintype "passive"))
      (node (ref "S2") (pin "2") (pinfunction "2_2") (pintype "passive"))
      (node (ref "S3") (pin "2") (pinfunction "2_2") (pintype "passive"))
      (node (ref "S4") (pin "2") (pinfunction "2_2") (pintype "passive"))
      (node (ref "SJ1") (pin "1") (pinfunction "1_1") (pintype "passive"))
      (node (ref "SUPER-STEPDOWN1") (pin "GND") (pinfunction "GND_GND") (pintype "bidirectional"))
      (node (ref "SUPER-STEPDOWN1") (pin "IN-") (pinfunction "IN-_IN-") (pintype "bidirectional"))
      (node (ref "U1") (pin "1") (pinfunction "GND_1") (pintype "power_in"))
      (node (ref "U10") (pin "1") (pinfunction "ADDR_1") (pintype "input"))
      (node (ref "U10") (pin "3") (pinfunction "GND_3") (pintype "power_in"))
      (node (ref "U11") (pin "2") (pinfunction "C_2") (pintype "passive"))
      (node (ref "U12") (pin "10") (pinfunction "GND_10") (pintype "power_in"))
      (node (ref "U12") (pin "12") (pinfunction "GND_12") (pintype "power_in"))
      (node (ref "U12") (pin "13") (pinfunction "GND_13") (pintype "power_in"))
      (node (ref "U12") (pin "24") (pinfunction "GND_24") (pintype "power_in"))
      (node (ref "U13") (pin "2") (pinfunction "C_2") (pintype "passive"))
      (node (ref "U2") (pin "1") (pinfunction "GND_1") (pintype "power_in"))
      (node (ref "U2") (pin "15") (pinfunction "GND_15") (pintype "power_in"))
      (node (ref "U2") (pin "38") (pinfunction "GND_38") (pintype "power_in"))
      (node (ref "U2") (pin "39_1") (pinfunction "GND_39_1") (pintype "power_in"))
      (node (ref "U2") (pin "39_10") (pinfunction "GND_39_10") (pintype "power_in"))
      (node (ref "U2") (pin "39_11") (pinfunction "GND_39_11") (pintype "power_in"))
      (node (ref "U2") (pin "39_12") (pinfunction "GND_39_12") (pintype "power_in"))
      (node (ref "U2") (pin "39_13") (pinfunction "GND_39_13") (pintype "power_in"))
      (node (ref "U2") (pin "39_14") (pinfunction "GND_39_14") (pintype "power_in"))
      (node (ref "U2") (pin "39_15") (pinfunction "GND_39_15") (pintype "power_in"))
      (node (ref "U2") (pin "39_16") (pinfunction "GND_39_16") (pintype "power_in"))
      (node (ref "U2") (pin "39_17") (pinfunction "GND_39_17") (pintype "power_in"))
      (node (ref "U2") (pin "39_18") (pinfunction "GND_39_18") (pintype "power_in"))
      (node (ref "U2") (pin "39_19") (pinfunction "GND_39_19") (pintype "power_in"))
      (node (ref "U2") (pin "39_2") (pinfunction "GND_39_2") (pintype "power_in"))
      (node (ref "U2") (pin "39_20") (pinfunction "GND_39_20") (pintype "power_in"))
      (node (ref "U2") (pin "39_21") (pinfunction "GND_39_21") (pintype "power_in"))
      (node (ref "U2") (pin "39_3") (pinfunction "GND_39_3") (pintype "power_in"))
      (node (ref "U2") (pin "39_4") (pinfunction "GND_39_4") (pintype "power_in"))
      (node (ref "U2") (pin "39_5") (pinfunction "GND_39_5") (pintype "power_in"))
      (node (ref "U2") (pin "39_6") (pinfunction "GND_39_6") (pintype "power_in"))
      (node (ref "U2") (pin "39_7") (pinfunction "GND_39_7") (pintype "power_in"))
      (node (ref "U2") (pin "39_8") (pinfunction "GND_39_8") (pintype "power_in"))
      (node (ref "U2") (pin "39_9") (pinfunction "GND_39_9") (pintype "power_in"))
      (node (ref "U3") (pin "1") (pinfunction "ADJ/GND_1") (pintype "power_in"))
      (node (ref "U4") (pin "2") (pinfunction "C_2") (pintype "passive"))
      (node (ref "U5") (pin "2") (pinfunction "C_2") (pintype "passive"))
      (node (ref "U6") (pin "2") (pinfunction "C_2") (pintype "passive"))
      (node (ref "U7") (pin "1") (pinfunction "GND_1") (pintype "power_in"))
      (node (ref "U8") (pin "1") (pinfunction "ADJ/GND_1") (pintype "power_in"))
      (node (ref "U9") (pin "1") (pinfunction "GND_1") (pintype "power_in"))
      (node (ref "U9") (pin "15") (pinfunction "GND_15") (pintype "power_in"))
      (node (ref "U9") (pin "38") (pinfunction "GND_38") (pintype "power_in"))
      (node (ref "U9") (pin "39_1") (pinfunction "GND_39_1") (pintype "power_in"))
      (node (ref "U9") (pin "39_10") (pinfunction "GND_39_10") (pintype "power_in"))
      (node (ref "U9") (pin "39_11") (pinfunction "GND_39_11") (pintype "power_in"))
      (node (ref "U9") (pin "39_12") (pinfunction "GND_39_12") (pintype "power_in"))
      (node (ref "U9") (pin "39_13") (pinfunction "GND_39_13") (pintype "power_in"))
      (node (ref "U9") (pin "39_14") (pinfunction "GND_39_14") (pintype "power_in"))
      (node (ref "U9") (pin "39_15") (pinfunction "GND_39_15") (pintype "power_in"))
      (node (ref "U9") (pin "39_16") (pinfunction "GND_39_16") (pintype "power_in"))
      (node (ref "U9") (pin "39_17") (pinfunction "GND_39_17") (pintype "power_in"))
      (node (ref "U9") (pin "39_18") (pinfunction "GND_39_18") (pintype "power_in"))
      (node (ref "U9") (pin "39_19") (pinfunction "GND_39_19") (pintype "power_in"))
      (node (ref "U9") (pin "39_2") (pinfunction "GND_39_2") (pintype "power_in"))
      (node (ref "U9") (pin "39_20") (pinfunction "GND_39_20") (pintype "power_in"))
      (node (ref "U9") (pin "39_21") (pinfunction "GND_39_21") (pintype "power_in"))
      (node (ref "U9") (pin "39_3") (pinfunction "GND_39_3") (pintype "power_in"))
      (node (ref "U9") (pin "39_4") (pinfunction "GND_39_4") (pintype "power_in"))
      (node (ref "U9") (pin "39_5") (pinfunction "GND_39_5") (pintype "power_in"))
      (node (ref "U9") (pin "39_6") (pinfunction "GND_39_6") (pintype "power_in"))
      (node (ref "U9") (pin "39_7") (pinfunction "GND_39_7") (pintype "power_in"))
      (node (ref "U9") (pin "39_8") (pinfunction "GND_39_8") (pintype "power_in"))
      (node (ref "U9") (pin "39_9") (pinfunction "GND_39_9") (pintype "power_in"))
      (node (ref "X2") (pin "2") (pinfunction "1_2") (pintype "passive"))
      (node (ref "X4") (pin "3") (pinfunction "1_3") (pintype "passive"))
      (node (ref "X6") (pin "4") (pinfunction "1_4") (pintype "passive"))
      (node (ref "X7") (pin "1") (pinfunction "S_1") (pintype "passive"))
    )
    (net (code "20") (name "GND-BATT") (class "Default")
      (node (ref "K3") (pin "NO") (pinfunction "NO_NO") (pintype "passive"))
      (node (ref "X1") (pin "2") (pinfunction "1_2") (pintype "passive"))
      (node (ref "X2") (pin "1") (pinfunction "1_1") (pintype "passive"))
    )
    (net (code "21") (name "IO0") (class "Default")
      (node (ref "C11") (pin "1") (pinfunction "1_1") (pintype "passive"))
      (node (ref "Q2") (pin "3") (pinfunction "C_3") (pintype "passive"))
      (node (ref "R5") (pin "1") (pinfunction "1_1") (pintype "passive"))
      (node (ref "S2") (pin "1") (pinfunction "1_1") (pintype "passive"))
      (node (ref "U2") (pin "25") (pinfunction "IO0_25") (pintype "bidirectional"))
    )
    (net (code "22") (name "IO01") (class "Default")
      (node (ref "C18") (pin "1") (pinfunction "1_1") (pintype "passive"))
      (node (ref "Q9") (pin "3") (pinfunction "C_3") (pintype "passive"))
      (node (ref "R28") (pin "1") (pinfunction "1_1") (pintype "passive"))
      (node (ref "S4") (pin "1") (pinfunction "1_1") (pintype "passive"))
      (node (ref "U9") (pin "25") (pinfunction "IO0_25") (pintype "bidirectional"))
    )
    (net (code "23") (name "M1") (class "Default")
      (node (ref "EBYTEE220-900T22D1") (pin "M1") (pinfunction "M1_M1") (pintype "bidirectional"))
      (node (ref "U9") (pin "29") (pinfunction "IO5_29") (pintype "bidirectional"))
    )
    (net (code "24") (name "M2_BATT-BACK-SWITCH") (class "Default")
      (node (ref "R36") (pin "2") (pinfunction "2_2") (pintype "passive"))
      (node (ref "U9") (pin "24") (pinfunction "IO2_24") (pintype "bidirectional"))
    )
    (net (code "25") (name "M2_RX") (class "Default")
      (node (ref "D14") (pin "A") (pinfunction "A_A") (pintype "passive"))
      (node (ref "K4") (pin "P2") (pinfunction "P_P2") (pintype "passive"))
      (node (ref "R30") (pin "2") (pinfunction "2_2") (pintype "passive"))
    )
    (net (code "26") (name "M2_SWITCHGPS") (class "Default")
      (node (ref "R22") (pin "2") (pinfunction "2_2") (pintype "passive"))
      (node (ref "U9") (pin "11") (pinfunction "IO26_11") (pintype "bidirectional"))
    )
    (net (code "27") (name "M2_TX") (class "Default")
      (node (ref "K4") (pin "P1") (pinfunction "P_P1") (pintype "passive"))
      (node (ref "U9") (pin "27") (pinfunction "IO16_27") (pintype "bidirectional"))
    )
    (net (code "28") (name "Net-(C22-Pad1)") (class "Default")
      (node (ref "C22") (pin "1") (pinfunction "1_1") (pintype "passive"))
      (node (ref "C23") (pin "1") (pinfunction "1_1") (pintype "passive"))
      (node (ref "R32") (pin "2") (pinfunction "2_2") (pintype "passive"))
    )
    (net (code "29") (name "Net-(D1-PadA)") (class "Default")
      (node (ref "D1") (pin "A") (pinfunction "A_A") (pintype "passive"))
      (node (ref "SUPER-STEPDOWN1") (pin "+5V") (pinfunction "+5V_+5V") (pintype "bidirectional"))
    )
    (net (code "30") (name "Net-(D3-PadA)") (class "Default")
      (node (ref "D3") (pin "A") (pinfunction "A_A") (pintype "passive"))
      (node (ref "R3") (pin "1") (pinfunction "1_1") (pintype "passive"))
    )
    (net (code "31") (name "Net-(D9-PadA)") (class "Default")
      (node (ref "D9") (pin "A") (pinfunction "A_A") (pintype "passive"))
      (node (ref "R17") (pin "1") (pinfunction "1_1") (pintype "passive"))
    )
    (net (code "32") (name "Net-(D10-PadA)") (class "Default")
      (node (ref "D10") (pin "A") (pinfunction "A_A") (pintype "passive"))
      (node (ref "R18") (pin "1") (pinfunction "1_1") (pintype "passive"))
    )
    (net (code "33") (name "Net-(D11-PadA)") (class "Default")
      (node (ref "D11") (pin "A") (pinfunction "A_A") (pintype "passive"))
      (node (ref "R19") (pin "1") (pinfunction "1_1") (pintype "passive"))
    )
    (net (code "34") (name "Net-(D12-PadA)") (class "Default")
      (node (ref "D12") (pin "A") (pinfunction "A_A") (pintype "passive"))
      (node (ref "R20") (pin "1") (pinfunction "1_1") (pintype "passive"))
    )
    (net (code "35") (name "Net-(D14-K)") (class "Default")
      (node (ref "D14") (pin "C") (pinfunction "K_C") (pintype "passive"))
      (node (ref "U9") (pin "28") (pinfunction "IO17_28") (pintype "bidirectional"))
    )
    (net (code "36") (name "Net-(D15-K)") (class "Default")
      (node (ref "D15") (pin "C") (pinfunction "K_C") (pintype "passive"))
      (node (ref "U2") (pin "28") (pinfunction "IO17_28") (pintype "bidirectional"))
    )
    (net (code "37") (name "Net-(D16-PadA)") (class "Default")
      (node (ref "D16") (pin "A") (pinfunction "A_A") (pintype "passive"))
      (node (ref "R33") (pin "1") (pinfunction "1_1") (pintype "passive"))
    )
    (net (code "38") (name "Net-(D17-K)") (class "Default")
      (node (ref "D17") (pin "C") (pinfunction "K_C") (pintype "passive"))
      (node (ref "R34") (pin "2") (pinfunction "2_2") (pintype "passive"))
    )
    (net (code "39") (name "Net-(K1A-2)") (class "Default")
      (node (ref "D4") (pin "A") (pinfunction "A_A") (pintype "passive"))
      (node (ref "K1") (pin "16") (pinfunction "2_16") (pintype "passive"))
      (node (ref "Q4") (pin "3") (pinfunction "C_3") (pintype "passive"))
    )
    (net (code "40") (name "Net-(K2A-2)") (class "Default")
      (node (ref "D5") (pin "A") (pinfunction "A_A") (pintype "passive"))
      (node (ref "K2") (pin "16") (pinfunction "2_16") (pintype "passive"))
      (node (ref "Q5") (pin "3") (pinfunction "C_3") (pintype "passive"))
    )
    (net (code "41") (name "Net-(K4A-2)") (class "Default")
      (node (ref "D13") (pin "A") (pinfunction "A_A") (pintype "passive"))
      (node (ref "K4") (pin "16") (pinfunction "2_16") (pintype "passive"))
      (node (ref "Q10") (pin "3") (pinfunction "C_3") (pintype "passive"))
    )
    (net (code "42") (name "Net-(K5A-2)") (class "Default")
      (node (ref "D18") (pin "A") (pinfunction "A_A") (pintype "passive"))
      (node (ref "K5") (pin "16") (pinfunction "2_16") (pintype "passive"))
      (node (ref "Q11") (pin "3") (pinfunction "C_3") (pintype "passive"))
    )
    (net (code "43") (name "Net-(K5B-S)") (class "Default")
      (node (ref "K5") (pin "S1") (pinfunction "S_S1") (pintype "passive"))
      (node (ref "X7") (pin "2") (pinfunction "S_2") (pintype "passive"))
    )
    (net (code "44") (name "Net-(Q1-B)") (class "Default")
      (node (ref "Q1") (pin "1") (pinfunction "B_1") (pintype "passive"))
      (node (ref "R1") (pin "2") (pinfunction "2_2") (pintype "passive"))
    )
    (net (code "45") (name "Net-(Q2-B)") (class "Default")
      (node (ref "Q2") (pin "1") (pinfunction "B_1") (pintype "passive"))
      (node (ref "R2") (pin "2") (pinfunction "2_2") (pintype "passive"))
    )
    (net (code "46") (name "Net-(Q4-B)") (class "Default")
      (node (ref "Q4") (pin "1") (pinfunction "B_1") (pintype "passive"))
      (node (ref "U4") (pin "3") (pinfunction "ET_3") (pintype "passive"))
    )
    (net (code "47") (name "Net-(Q5-B)") (class "Default")
      (node (ref "Q5") (pin "1") (pinfunction "B_1") (pintype "passive"))
      (node (ref "U5") (pin "3") (pinfunction "ET_3") (pintype "passive"))
    )
    (net (code "48") (name "Net-(Q6-B)") (class "Default")
      (node (ref "Q6") (pin "1") (pinfunction "B_1") (pintype "passive"))
      (node (ref "U6") (pin "3") (pinfunction "ET_3") (pintype "passive"))
    )
    (net (code "49") (name "Net-(Q6-C)") (class "Default")
      (node (ref "D6") (pin "A") (pinfunction "A_A") (pintype "passive"))
      (node (ref "K3") (pin "A2") (pinfunction "A2_A2") (pintype "passive"))
      (node (ref "Q6") (pin "3") (pinfunction "C_3") (pintype "passive"))
    )
    (net (code "50") (name "Net-(Q8-B)") (class "Default")
      (node (ref "Q8") (pin "1") (pinfunction "B_1") (pintype "passive"))
      (node (ref "R25") (pin "2") (pinfunction "2_2") (pintype "passive"))
    )
    (net (code "51") (name "Net-(Q9-B)") (class "Default")
      (node (ref "Q9") (pin "1") (pinfunction "B_1") (pintype "passive"))
      (node (ref "R26") (pin "2") (pinfunction "2_2") (pintype "passive"))
    )
    (net (code "52") (name "Net-(Q10-B)") (class "Default")
      (node (ref "Q10") (pin "1") (pinfunction "B_1") (pintype "passive"))
      (node (ref "U11") (pin "3") (pinfunction "ET_3") (pintype "passive"))
    )
    (net (code "53") (name "Net-(Q11-B)") (class "Default")
      (node (ref "Q11") (pin "1") (pinfunction "B_1") (pintype "passive"))
      (node (ref "U13") (pin "3") (pinfunction "ET_3") (pintype "passive"))
    )
    (net (code "54") (name "Net-(Q12-C)") (class "Default")
      (node (ref "D16") (pin "C") (pinfunction "C_C") (pintype "passive"))
      (node (ref "Q12") (pin "3") (pinfunction "C_3") (pintype "passive"))
    )
    (net (code "55") (name "Net-(U1-V3)") (class "Default")
      (node (ref "C3") (pin "1") (pinfunction "1_1") (pintype "passive"))
      (node (ref "U1") (pin "4") (pinfunction "V3_4") (pintype "power_in"))
    )
    (net (code "56") (name "Net-(U1-XI)") (class "Default")
      (node (ref "C4") (pin "2") (pinfunction "2_2") (pintype "passive"))
      (node (ref "Q3") (pin "2") (pinfunction "2_2") (pintype "passive"))
      (node (ref "U1") (pin "7") (pinfunction "XI_7") (pintype "input"))
    )
    (net (code "57") (name "Net-(U1-XO)") (class "Default")
      (node (ref "C5") (pin "2") (pinfunction "2_2") (pintype "passive"))
      (node (ref "Q3") (pin "1") (pinfunction "1_1") (pintype "passive"))
      (node (ref "U1") (pin "8") (pinfunction "XO_8") (pintype "output"))
    )
    (net (code "58") (name "Net-(U4-A)") (class "Default")
      (node (ref "R11") (pin "1") (pinfunction "1_1") (pintype "passive"))
      (node (ref "U4") (pin "1") (pinfunction "A_1") (pintype "passive"))
    )
    (net (code "59") (name "Net-(U4-CT)") (class "Default")
      (node (ref "R12") (pin "2") (pinfunction "2_2") (pintype "passive"))
      (node (ref "U4") (pin "4") (pinfunction "CT_4") (pintype "passive"))
    )
    (net (code "60") (name "Net-(U5-A)") (class "Default")
      (node (ref "R13") (pin "1") (pinfunction "1_1") (pintype "passive"))
      (node (ref "U5") (pin "1") (pinfunction "A_1") (pintype "passive"))
    )
    (net (code "61") (name "Net-(U5-CT)") (class "Default")
      (node (ref "R14") (pin "2") (pinfunction "2_2") (pintype "passive"))
      (node (ref "U5") (pin "4") (pinfunction "CT_4") (pintype "passive"))
    )
    (net (code "62") (name "Net-(U6-A)") (class "Default")
      (node (ref "R23") (pin "1") (pinfunction "1_1") (pintype "passive"))
      (node (ref "U6") (pin "1") (pinfunction "A_1") (pintype "passive"))
    )
    (net (code "63") (name "Net-(U6-CT)") (class "Default")
      (node (ref "R24") (pin "2") (pinfunction "2_2") (pintype "passive"))
      (node (ref "U6") (pin "4") (pinfunction "CT_4") (pintype "passive"))
    )
    (net (code "64") (name "Net-(U7-V3)") (class "Default")
      (node (ref "C16") (pin "1") (pinfunction "1_1") (pintype "passive"))
      (node (ref "U7") (pin "4") (pinfunction "V3_4") (pintype "power_in"))
    )
    (net (code "65") (name "Net-(U7-XI)") (class "Default")
      (node (ref "C12") (pin "2") (pinfunction "2_2") (pintype "passive"))
      (node (ref "Q7") (pin "2") (pinfunction "2_2") (pintype "passive"))
      (node (ref "U7") (pin "7") (pinfunction "XI_7") (pintype "input"))
    )
    (net (code "66") (name "Net-(U7-XO)") (class "Default")
      (node (ref "C13") (pin "2") (pinfunction "2_2") (pintype "passive"))
      (node (ref "Q7") (pin "1") (pinfunction "1_1") (pintype "passive"))
      (node (ref "U7") (pin "8") (pinfunction "XO_8") (pintype "output"))
    )
    (net (code "67") (name "Net-(U11-A)") (class "Default")
      (node (ref "R22") (pin "1") (pinfunction "1_1") (pintype "passive"))
      (node (ref "U11") (pin "1") (pinfunction "A_1") (pintype "passive"))
    )
    (net (code "68") (name "Net-(U11-CT)") (class "Default")
      (node (ref "R29") (pin "2") (pinfunction "2_2") (pintype "passive"))
      (node (ref "U11") (pin "4") (pinfunction "CT_4") (pintype "passive"))
    )
    (net (code "69") (name "Net-(U12-VCC_RF)") (class "Default")
      (node (ref "R32") (pin "1") (pinfunction "1_1") (pintype "passive"))
      (node (ref "U12") (pin "9") (pinfunction "VCC_RF_9") (pintype "output"))
    )
    (net (code "70") (name "Net-(U13-A)") (class "Default")
      (node (ref "R36") (pin "1") (pinfunction "1_1") (pintype "passive"))
      (node (ref "U13") (pin "1") (pinfunction "A_1") (pintype "passive"))
    )
    (net (code "71") (name "Net-(U13-CT)") (class "Default")
      (node (ref "R37") (pin "2") (pinfunction "2_2") (pintype "passive"))
      (node (ref "U13") (pin "4") (pinfunction "CT_4") (pintype "passive"))
    )
    (net (code "72") (name "OUT+") (class "Default")
      (node (ref "ADS1") (pin "VDD") (pinfunction "VDD_VDD") (pintype "bidirectional"))
      (node (ref "ADS2") (pin "VDD") (pinfunction "VDD_VDD") (pintype "bidirectional"))
      (node (ref "C19") (pin "1") (pinfunction "1_1") (pintype "passive"))
      (node (ref "C21") (pin "1") (pinfunction "1_1") (pintype "passive"))
      (node (ref "C6") (pin "+") (pinfunction "+_+") (pintype "passive"))
      (node (ref "C7") (pin "1") (pinfunction "1_1") (pintype "passive"))
      (node (ref "C8") (pin "1") (pinfunction "1_1") (pintype "passive"))
      (node (ref "D1") (pin "C") (pinfunction "K_C") (pintype "passive"))
      (node (ref "D13") (pin "C") (pinfunction "K_C") (pintype "passive"))
      (node (ref "D18") (pin "C") (pinfunction "K_C") (pintype "passive"))
      (node (ref "D2") (pin "C") (pinfunction "K_C") (pintype "passive"))
      (node (ref "D4") (pin "C") (pinfunction "K_C") (pintype "passive"))
      (node (ref "D5") (pin "C") (pinfunction "K_C") (pintype "passive"))
      (node (ref "D6") (pin "C") (pinfunction "K_C") (pintype "passive"))
      (node (ref "D7") (pin "C") (pinfunction "K_C") (pintype "passive"))
      (node (ref "D8") (pin "C") (pinfunction "K_C") (pintype "passive"))
      (node (ref "EBYTEE220-900T22D1") (pin "VCC") (pinfunction "VCC_VCC") (pintype "bidirectional"))
      (node (ref "K1") (pin "1") (pinfunction "1_1") (pintype "passive"))
      (node (ref "K2") (pin "1") (pinfunction "1_1") (pintype "passive"))
      (node (ref "K3") (pin "A1") (pinfunction "A1_A1") (pintype "passive"))
      (node (ref "K4") (pin "1") (pinfunction "1_1") (pintype "passive"))
      (node (ref "K5") (pin "1") (pinfunction "1_1") (pintype "passive"))
      (node (ref "NEO-6MGPS1") (pin "5V") (pinfunction "5V_5V") (pintype "bidirectional"))
      (node (ref "R12") (pin "1") (pinfunction "1_1") (pintype "passive"))
      (node (ref "R14") (pin "1") (pinfunction "1_1") (pintype "passive"))
      (node (ref "R24") (pin "1") (pinfunction "1_1") (pintype "passive"))
      (node (ref "R29") (pin "1") (pinfunction "1_1") (pintype "passive"))
      (node (ref "R3") (pin "2") (pinfunction "2_2") (pintype "passive"))
      (node (ref "R37") (pin "1") (pinfunction "1_1") (pintype "passive"))
      (node (ref "U10") (pin "8") (pinfunction "VDD_8") (pintype "power_in"))
      (node (ref "U3") (pin "3") (pinfunction "VIN_3") (pintype "input"))
      (node (ref "U8") (pin "3") (pinfunction "VIN_3") (pintype "input"))
      (node (ref "X6") (pin "1") (pinfunction "1_1") (pintype "passive"))
    )
    (net (code "73") (name "OUT-BATT") (class "Default")
      (node (ref "D8") (pin "A") (pinfunction "A_A") (pintype "passive"))
      (node (ref "K5") (pin "P1") (pinfunction "P_P1") (pintype "passive"))
    )
    (net (code "74") (name "OUT1") (class "Default")
      (node (ref "SV1") (pin "1") (pinfunction "1_1") (pintype "passive"))
      (node (ref "U9") (pin "37") (pinfunction "IO23_37") (pintype "bidirectional"))
    )
    (net (code "75") (name "OUT2") (class "Default")
      (node (ref "SV1") (pin "2") (pinfunction "2_2") (pintype "passive"))
      (node (ref "U9") (pin "26") (pinfunction "IO4_26") (pintype "bidirectional"))
    )
    (net (code "76") (name "OUT3") (class "Default")
      (node (ref "SV1") (pin "3") (pinfunction "3_3") (pintype "passive"))
      (node (ref "U9") (pin "23") (pinfunction "IO15_23") (pintype "bidirectional"))
    )
    (net (code "77") (name "OUT4") (class "Default")
      (node (ref "SV1") (pin "4") (pinfunction "4_4") (pintype "passive"))
      (node (ref "U9") (pin "16") (pinfunction "IO13_16") (pintype "bidirectional"))
    )
    (net (code "78") (name "OUT5") (class "Default")
      (node (ref "SV1") (pin "5") (pinfunction "5_5") (pintype "passive"))
      (node (ref "U9") (pin "14") (pinfunction "IO12_14") (pintype "bidirectional"))
    )
    (net (code "79") (name "OUT6") (class "Default")
      (node (ref "SV1") (pin "6") (pinfunction "6_6") (pintype "passive"))
      (node (ref "U9") (pin "13") (pinfunction "IO14_13") (pintype "bidirectional"))
    )
    (net (code "80") (name "OUT7") (class "Default")
      (node (ref "SV1") (pin "7") (pinfunction "7_7") (pintype "passive"))
      (node (ref "U9") (pin "12") (pinfunction "IO27_12") (pintype "bidirectional"))
    )
    (net (code "81") (name "OUT8") (class "Default")
      (node (ref "SV1") (pin "8") (pinfunction "8_8") (pintype "passive"))
      (node (ref "U9") (pin "9") (pinfunction "IO33_9") (pintype "bidirectional"))
    )
    (net (code "82") (name "OUT9") (class "Default")
      (node (ref "SV1") (pin "9") (pinfunction "9_9") (pintype "passive"))
      (node (ref "U9") (pin "8") (pinfunction "IO32_8") (pintype "bidirectional"))
    )
    (net (code "83") (name "PB-PWR") (class "Default")
      (node (ref "R9") (pin "2") (pinfunction "2_2") (pintype "passive"))
      (node (ref "X3") (pin "3") (pinfunction "1_3") (pintype "passive"))
    )
    (net (code "84") (name "RF_IN") (class "Default")
      (node (ref "C22") (pin "2") (pinfunction "2_2") (pintype "passive"))
      (node (ref "J3") (pin "3") (pinfunction "SIG_3") (pintype "passive"))
      (node (ref "U12") (pin "11") (pinfunction "RF_IN_11") (pintype "input"))
    )
    (net (code "85") (name "RTS") (class "Default")
      (node (ref "Q1") (pin "2") (pinfunction "E_2") (pintype "passive"))
      (node (ref "R2") (pin "1") (pinfunction "1_1") (pintype "passive"))
      (node (ref "U1") (pin "14") (pinfunction "~{RTS}_14") (pintype "output"))
    )
    (net (code "86") (name "RTS1") (class "Default")
      (node (ref "Q8") (pin "2") (pinfunction "E_2") (pintype "passive"))
      (node (ref "R26") (pin "1") (pinfunction "1_1") (pintype "passive"))
      (node (ref "U7") (pin "14") (pinfunction "~{RTS}_14") (pintype "output"))
    )
    (net (code "87") (name "RX") (class "Default")
      (node (ref "D10") (pin "C") (pinfunction "C_C") (pintype "passive"))
      (node (ref "U1") (pin "3") (pinfunction "RXD_3") (pintype "input"))
      (node (ref "U2") (pin "35") (pinfunction "TXD0_35") (pintype "bidirectional"))
    )
    (net (code "88") (name "RX1") (class "Default")
      (node (ref "D12") (pin "C") (pinfunction "C_C") (pintype "passive"))
      (node (ref "U7") (pin "3") (pinfunction "RXD_3") (pintype "input"))
      (node (ref "U9") (pin "35") (pinfunction "TXD0_35") (pintype "bidirectional"))
    )
    (net (code "89") (name "RXLORA_CONFIG") (class "Default")
      (node (ref "K1") (pin "S1") (pinfunction "S_S1") (pintype "passive"))
      (node (ref "X4") (pin "2") (pinfunction "1_2") (pintype "passive"))
    )
    (net (code "90") (name "RXLORA_MICRO") (class "Default")
      (node (ref "D15") (pin "A") (pinfunction "A_A") (pintype "passive"))
      (node (ref "K1") (pin "O1") (pinfunction "O_O1") (pintype "passive"))
      (node (ref "R31") (pin "1") (pinfunction "1_1") (pintype "passive"))
    )
    (net (code "91") (name "RX_GPS") (class "Default")
      (node (ref "NEO-6MGPS1") (pin "RX") (pinfunction "RX_RX") (pintype "bidirectional"))
      (node (ref "SJ2") (pin "2") (pinfunction "2_2") (pintype "passive"))
      (node (ref "U12") (pin "21") (pinfunction "RXD/SPI_MOSI_21") (pintype "input"))
    )
    (net (code "92") (name "RX_GPS1") (class "Default")
      (node (ref "K4") (pin "O2") (pinfunction "O_O2") (pintype "passive"))
      (node (ref "SJ2") (pin "1") (pinfunction "1_1") (pintype "passive"))
    )
    (net (code "93") (name "RX_LORA") (class "Default")
      (node (ref "EBYTEE220-900T22D1") (pin "RXD") (pinfunction "RXD_RXD") (pintype "bidirectional"))
      (node (ref "K1") (pin "P1") (pinfunction "P_P1") (pintype "passive"))
      (node (ref "K4") (pin "S2") (pinfunction "S_S2") (pintype "passive"))
    )
    (net (code "94") (name "RX_MICRO") (class "Default")
      (node (ref "U2") (pin "13") (pinfunction "IO14_13") (pintype "bidirectional"))
      (node (ref "U9") (pin "30") (pinfunction "IO18_30") (pintype "bidirectional"))
    )
    (net (code "95") (name "SCL") (class "Default")
      (node (ref "ADS1") (pin "SCL") (pinfunction "SCL_SCL") (pintype "bidirectional"))
      (node (ref "U10") (pin "10") (pinfunction "SCL_10") (pintype "input"))
      (node (ref "U2") (pin "36") (pinfunction "IO22_36") (pintype "bidirectional"))
      (node (ref "X6") (pin "3") (pinfunction "1_3") (pintype "passive"))
    )
    (net (code "96") (name "SCL1") (class "Default")
      (node (ref "ADS2") (pin "SCL") (pinfunction "SCL_SCL") (pintype "bidirectional"))
      (node (ref "U9") (pin "36") (pinfunction "IO22_36") (pintype "bidirectional"))
      (node (ref "X8") (pin "1") (pinfunction "1_1") (pintype "passive"))
    )
    (net (code "97") (name "SDA") (class "Default")
      (node (ref "ADS1") (pin "SDA") (pinfunction "SDA_SDA") (pintype "bidirectional"))
      (node (ref "U10") (pin "9") (pinfunction "SDA_9") (pintype "bidirectional"))
      (node (ref "U2") (pin "33") (pinfunction "IO21_33") (pintype "bidirectional"))
      (node (ref "X6") (pin "2") (pinfunction "1_2") (pintype "passive"))
    )
    (net (code "98") (name "SDA1") (class "Default")
      (node (ref "ADS2") (pin "SDA") (pinfunction "SDA_SDA") (pintype "bidirectional"))
      (node (ref "U9") (pin "33") (pinfunction "IO21_33") (pintype "bidirectional"))
      (node (ref "X8") (pin "2") (pinfunction "1_2") (pintype "passive"))
    )
    (net (code "99") (name "TIMEPULSE") (class "Default")
      (node (ref "Q12") (pin "1") (pinfunction "B_1") (pintype "passive"))
      (node (ref "U12") (pin "3") (pinfunction "TIMEPULSE_3") (pintype "output"))
    )
    (net (code "100") (name "TX") (class "Default")
      (node (ref "D9") (pin "C") (pinfunction "C_C") (pintype "passive"))
      (node (ref "U1") (pin "2") (pinfunction "TXD_2") (pintype "output"))
      (node (ref "U2") (pin "34") (pinfunction "RXD0_34") (pintype "bidirectional"))
    )
    (net (code "101") (name "TX1") (class "Default")
      (node (ref "D11") (pin "C") (pinfunction "C_C") (pintype "passive"))
      (node (ref "U7") (pin "2") (pinfunction "TXD_2") (pintype "output"))
      (node (ref "U9") (pin "34") (pinfunction "RXD0_34") (pintype "bidirectional"))
    )
    (net (code "102") (name "TXLORA_CONFIG") (class "Default")
      (node (ref "K1") (pin "S2") (pinfunction "S_S2") (pintype "passive"))
      (node (ref "X4") (pin "1") (pinfunction "1_1") (pintype "passive"))
    )
    (net (code "103") (name "TXLORA_MICRO") (class "Default")
      (node (ref "K1") (pin "O2") (pinfunction "O_O2") (pintype "passive"))
      (node (ref "U2") (pin "27") (pinfunction "IO16_27") (pintype "bidirectional"))
    )
    (net (code "104") (name "TX_GPS") (class "Default")
      (node (ref "NEO-6MGPS1") (pin "TX") (pinfunction "TX_TX") (pintype "bidirectional"))
      (node (ref "SJ3") (pin "2") (pinfunction "2_2") (pintype "passive"))
      (node (ref "U12") (pin "20") (pinfunction "TXD/SPI_MISO_20") (pintype "output"))
    )
    (net (code "105") (name "TX_GPS1") (class "Default")
      (node (ref "K4") (pin "O1") (pinfunction "O_O1") (pintype "passive"))
      (node (ref "SJ3") (pin "1") (pinfunction "1_1") (pintype "passive"))
    )
    (net (code "106") (name "TX_LORA") (class "Default")
      (node (ref "EBYTEE220-900T22D1") (pin "TXD") (pinfunction "TXD_TXD") (pintype "bidirectional"))
      (node (ref "K1") (pin "P2") (pinfunction "P_P2") (pintype "passive"))
      (node (ref "K4") (pin "S1") (pinfunction "S_S1") (pintype "passive"))
    )
    (net (code "107") (name "TX_MICRO") (class "Default")
      (node (ref "U2") (pin "23") (pinfunction "IO15_23") (pintype "bidirectional"))
      (node (ref "U9") (pin "31") (pinfunction "IO19_31") (pintype "bidirectional"))
    )
    (net (code "108") (name "USB1_N") (class "Default")
      (node (ref "J2") (pin "2") (pinfunction "D-_2") (pintype "passive"))
      (node (ref "U7") (pin "6") (pinfunction "UD-_6") (pintype "bidirectional"))
    )
    (net (code "109") (name "USB1_P") (class "Default")
      (node (ref "J2") (pin "3") (pinfunction "D+_3") (pintype "passive"))
      (node (ref "U7") (pin "5") (pinfunction "UD+_5") (pintype "bidirectional"))
    )
    (net (code "110") (name "USB_N") (class "Default")
      (node (ref "J1") (pin "2") (pinfunction "D-_2") (pintype "passive"))
      (node (ref "U1") (pin "6") (pinfunction "UD-_6") (pintype "bidirectional"))
    )
    (net (code "111") (name "USB_P") (class "Default")
      (node (ref "J1") (pin "3") (pinfunction "D+_3") (pintype "passive"))
      (node (ref "U1") (pin "5") (pinfunction "UD+_5") (pintype "bidirectional"))
    )
    (net (code "112") (name "VALVE") (class "Default")
      (node (ref "R13") (pin "2") (pinfunction "2_2") (pintype "passive"))
      (node (ref "U2") (pin "37") (pinfunction "IO23_37") (pintype "bidirectional"))
    )
    (net (code "113") (name "VALVE1") (class "Default")
      (node (ref "K2") (pin "S1") (pinfunction "S_S1") (pintype "passive"))
      (node (ref "X5") (pin "2") (pinfunction "1_2") (pintype "passive"))
    )
    (net (code "114") (name "VALVE2") (class "Default")
      (node (ref "K2") (pin "P1") (pinfunction "P_P1") (pintype "passive"))
      (node (ref "X5") (pin "1") (pinfunction "1_1") (pintype "passive"))
    )
    (net (code "115") (name "VCC") (class "Default")
      (node (ref "C9") (pin "1") (pinfunction "1_1") (pintype "passive"))
      (node (ref "R10") (pin "2") (pinfunction "2_2") (pintype "passive"))
      (node (ref "R17") (pin "2") (pinfunction "2_2") (pintype "passive"))
      (node (ref "R18") (pin "2") (pinfunction "2_2") (pintype "passive"))
      (node (ref "R31") (pin "2") (pinfunction "2_2") (pintype "passive"))
      (node (ref "R4") (pin "2") (pinfunction "2_2") (pintype "passive"))
      (node (ref "R5") (pin "2") (pinfunction "2_2") (pintype "passive"))
      (node (ref "R6") (pin "2") (pinfunction "2_2") (pintype "passive"))
      (node (ref "R7") (pin "2") (pinfunction "2_2") (pintype "passive"))
      (node (ref "R8") (pin "2") (pinfunction "2_2") (pintype "passive"))
      (node (ref "U2") (pin "2") (pinfunction "3V3_2") (pintype "power_in"))
      (node (ref "U3") (pin "2") (pinfunction "VOUT_2") (pintype "output"))
      (node (ref "U3") (pin "4") (pinfunction "VOUT_4") (pintype "output"))
    )
    (net (code "116") (name "VCC1") (class "Default")
      (node (ref "C20") (pin "1") (pinfunction "1_1") (pintype "passive"))
      (node (ref "D17") (pin "A") (pinfunction "A_A") (pintype "passive"))
      (node (ref "R19") (pin "2") (pinfunction "2_2") (pintype "passive"))
      (node (ref "R20") (pin "2") (pinfunction "2_2") (pintype "passive"))
      (node (ref "R27") (pin "2") (pinfunction "2_2") (pintype "passive"))
      (node (ref "R28") (pin "2") (pinfunction "2_2") (pintype "passive"))
      (node (ref "R30") (pin "1") (pinfunction "1_1") (pintype "passive"))
      (node (ref "R33") (pin "2") (pinfunction "2_2") (pintype "passive"))
      (node (ref "R35") (pin "2") (pinfunction "2_2") (pintype "passive"))
      (node (ref "U12") (pin "23") (pinfunction "VCC_23") (pintype "power_in"))
      (node (ref "U8") (pin "2") (pinfunction "VOUT_2") (pintype "output"))
      (node (ref "U8") (pin "4") (pinfunction "VOUT_4") (pintype "output"))
      (node (ref "U9") (pin "2") (pinfunction "3V3_2") (pintype "power_in"))
    )
    (net (code "117") (name "VUSB") (class "Default")
      (node (ref "C1") (pin "1") (pinfunction "1_1") (pintype "passive"))
      (node (ref "C2") (pin "+") (pinfunction "+_+") (pintype "passive"))
      (node (ref "D2") (pin "A") (pinfunction "A_A") (pintype "passive"))
      (node (ref "J1") (pin "1") (pinfunction "VUSB_1") (pintype "passive"))
      (node (ref "U1") (pin "16") (pinfunction "VCC_16") (pintype "power_in"))
    )
    (net (code "118") (name "VUSB1") (class "Default")
      (node (ref "C14") (pin "1") (pinfunction "1_1") (pintype "passive"))
      (node (ref "C15") (pin "+") (pinfunction "+_+") (pintype "passive"))
      (node (ref "D7") (pin "A") (pinfunction "A_A") (pintype "passive"))
      (node (ref "J2") (pin "1") (pinfunction "VUSB_1") (pintype "passive"))
      (node (ref "U7") (pin "16") (pinfunction "VCC_16") (pintype "power_in"))
    )
    (net (code "119") (name "unconnected-(ADS1-PadALRT)") (class "Default")
      (node (ref "ADS1") (pin "ALRT") (pinfunction "ALRT_ALRT") (pintype "bidirectional"))
    )
    (net (code "120") (name "unconnected-(ADS2-PadA1)") (class "Default")
      (node (ref "ADS2") (pin "A1") (pinfunction "A1_A1") (pintype "bidirectional"))
    )
    (net (code "121") (name "unconnected-(ADS2-PadA2)") (class "Default")
      (node (ref "ADS2") (pin "A2") (pinfunction "A2_A2") (pintype "bidirectional"))
    )
    (net (code "122") (name "unconnected-(ADS2-PadA3)") (class "Default")
      (node (ref "ADS2") (pin "A3") (pinfunction "A3_A3") (pintype "bidirectional"))
    )
    (net (code "123") (name "unconnected-(ADS2-PadALRT)") (class "Default")
      (node (ref "ADS2") (pin "ALRT") (pinfunction "ALRT_ALRT") (pintype "bidirectional"))
    )
    (net (code "124") (name "unconnected-(EBYTEE220-900T22D1-PadAUX)") (class "Default")
      (node (ref "EBYTEE220-900T22D1") (pin "AUX") (pinfunction "AUX_AUX") (pintype "bidirectional"))
    )
    (net (code "125") (name "unconnected-(J1-ID-Pad4)") (class "Default")
      (node (ref "J1") (pin "4") (pinfunction "ID_4") (pintype "passive"))
    )
    (net (code "126") (name "unconnected-(J2-ID-Pad4)") (class "Default")
      (node (ref "J2") (pin "4") (pinfunction "ID_4") (pintype "passive"))
    )
    (net (code "127") (name "unconnected-(K2B-O-PadO1)") (class "Default")
      (node (ref "K2") (pin "O1") (pinfunction "O_O1") (pintype "passive"))
    )
    (net (code "128") (name "unconnected-(K2C-O-PadO2)") (class "Default")
      (node (ref "K2") (pin "O2") (pinfunction "O_O2") (pintype "passive"))
    )
    (net (code "129") (name "unconnected-(K2C-P-PadP2)") (class "Default")
      (node (ref "K2") (pin "P2") (pinfunction "P_P2") (pintype "passive"))
    )
    (net (code "130") (name "unconnected-(K2C-S-PadS2)") (class "Default")
      (node (ref "K2") (pin "S2") (pinfunction "S_S2") (pintype "passive"))
    )
    (net (code "131") (name "unconnected-(K3-PadNC)") (class "Default")
      (node (ref "K3") (pin "NC") (pinfunction "NC_NC") (pintype "passive"))
    )
    (net (code "132") (name "unconnected-(K5B-O-PadO1)") (class "Default")
      (node (ref "K5") (pin "O1") (pinfunction "O_O1") (pintype "passive"))
    )
    (net (code "133") (name "unconnected-(K5C-O-PadO2)") (class "Default")
      (node (ref "K5") (pin "O2") (pinfunction "O_O2") (pintype "passive"))
    )
    (net (code "134") (name "unconnected-(K5C-P-PadP2)") (class "Default")
      (node (ref "K5") (pin "P2") (pinfunction "P_P2") (pintype "passive"))
    )
    (net (code "135") (name "unconnected-(K5C-S-PadS2)") (class "Default")
      (node (ref "K5") (pin "S2") (pinfunction "S_S2") (pintype "passive"))
    )
    (net (code "136") (name "unconnected-(U1-RS232-Pad15)") (class "Default")
      (node (ref "U1") (pin "15") (pinfunction "RS232_15") (pintype "input"))
    )
    (net (code "137") (name "unconnected-(U1-~{CTS}-Pad9)") (class "Default")
      (node (ref "U1") (pin "9") (pinfunction "~{CTS}_9") (pintype "input"))
    )
    (net (code "138") (name "unconnected-(U1-~{DCD}-Pad12)") (class "Default")
      (node (ref "U1") (pin "12") (pinfunction "~{DCD}_12") (pintype "input"))
    )
    (net (code "139") (name "unconnected-(U1-~{DSR}-Pad10)") (class "Default")
      (node (ref "U1") (pin "10") (pinfunction "~{DSR}_10") (pintype "input"))
    )
    (net (code "140") (name "unconnected-(U1-~{RI}-Pad11)") (class "Default")
      (node (ref "U1") (pin "11") (pinfunction "~{RI}_11") (pintype "input"))
    )
    (net (code "141") (name "unconnected-(U2-IO2-Pad24)") (class "Default")
      (node (ref "U2") (pin "24") (pinfunction "IO2_24") (pintype "bidirectional"))
    )
    (net (code "142") (name "unconnected-(U2-IO4-Pad26)") (class "Default")
      (node (ref "U2") (pin "26") (pinfunction "IO4_26") (pintype "bidirectional"))
    )
    (net (code "143") (name "unconnected-(U2-IO5-Pad29)") (class "Default")
      (node (ref "U2") (pin "29") (pinfunction "IO5_29") (pintype "bidirectional"))
    )
    (net (code "144") (name "unconnected-(U2-IO12-Pad14)") (class "Default")
      (node (ref "U2") (pin "14") (pinfunction "IO12_14") (pintype "bidirectional"))
    )
    (net (code "145") (name "unconnected-(U2-IO13-Pad16)") (class "Default")
      (node (ref "U2") (pin "16") (pinfunction "IO13_16") (pintype "bidirectional"))
    )
    (net (code "146") (name "unconnected-(U2-IO18-Pad30)") (class "Default")
      (node (ref "U2") (pin "30") (pinfunction "IO18_30") (pintype "bidirectional"))
    )
    (net (code "147") (name "unconnected-(U2-IO19-Pad31)") (class "Default")
      (node (ref "U2") (pin "31") (pinfunction "IO19_31") (pintype "bidirectional"))
    )
    (net (code "148") (name "unconnected-(U2-IO34-Pad6)") (class "Default")
      (node (ref "U2") (pin "6") (pinfunction "IO34_6") (pintype "input"))
    )
    (net (code "149") (name "unconnected-(U2-IO35-Pad7)") (class "Default")
      (node (ref "U2") (pin "7") (pinfunction "IO35_7") (pintype "input"))
    )
    (net (code "150") (name "unconnected-(U2-SCK{slash}CLK-Pad20)") (class "Default")
      (node (ref "U2") (pin "20") (pinfunction "SCK/CLK_20") (pintype "bidirectional"))
    )
    (net (code "151") (name "unconnected-(U2-SCS{slash}CMD-Pad19)") (class "Default")
      (node (ref "U2") (pin "19") (pinfunction "SCS/CMD_19") (pintype "bidirectional"))
    )
    (net (code "152") (name "unconnected-(U2-SDI{slash}SD1-Pad22)") (class "Default")
      (node (ref "U2") (pin "22") (pinfunction "SDI/SD1_22") (pintype "bidirectional"))
    )
    (net (code "153") (name "unconnected-(U2-SDO{slash}SD0-Pad21)") (class "Default")
      (node (ref "U2") (pin "21") (pinfunction "SDO/SD0_21") (pintype "bidirectional"))
    )
    (net (code "154") (name "unconnected-(U2-SENSOR_VN-Pad5)") (class "Default")
      (node (ref "U2") (pin "5") (pinfunction "SENSOR_VN_5") (pintype "input"))
    )
    (net (code "155") (name "unconnected-(U2-SENSOR_VP-Pad4)") (class "Default")
      (node (ref "U2") (pin "4") (pinfunction "SENSOR_VP_4") (pintype "input"))
    )
    (net (code "156") (name "unconnected-(U2-SHD{slash}SD2-Pad17)") (class "Default")
      (node (ref "U2") (pin "17") (pinfunction "SHD/SD2_17") (pintype "bidirectional"))
    )
    (net (code "157") (name "unconnected-(U2-SWP{slash}SD3-Pad18)") (class "Default")
      (node (ref "U2") (pin "18") (pinfunction "SWP/SD3_18") (pintype "bidirectional"))
    )
    (net (code "158") (name "unconnected-(U7-RS232-Pad15)") (class "Default")
      (node (ref "U7") (pin "15") (pinfunction "RS232_15") (pintype "input"))
    )
    (net (code "159") (name "unconnected-(U7-~{CTS}-Pad9)") (class "Default")
      (node (ref "U7") (pin "9") (pinfunction "~{CTS}_9") (pintype "input"))
    )
    (net (code "160") (name "unconnected-(U7-~{DCD}-Pad12)") (class "Default")
      (node (ref "U7") (pin "12") (pinfunction "~{DCD}_12") (pintype "input"))
    )
    (net (code "161") (name "unconnected-(U7-~{DSR}-Pad10)") (class "Default")
      (node (ref "U7") (pin "10") (pinfunction "~{DSR}_10") (pintype "input"))
    )
    (net (code "162") (name "unconnected-(U7-~{RI}-Pad11)") (class "Default")
      (node (ref "U7") (pin "11") (pinfunction "~{RI}_11") (pintype "input"))
    )
    (net (code "163") (name "unconnected-(U9-IO34-Pad6)") (class "Default")
      (node (ref "U9") (pin "6") (pinfunction "IO34_6") (pintype "input"))
    )
    (net (code "164") (name "unconnected-(U9-IO35-Pad7)") (class "Default")
      (node (ref "U9") (pin "7") (pinfunction "IO35_7") (pintype "input"))
    )
    (net (code "165") (name "unconnected-(U9-SCK{slash}CLK-Pad20)") (class "Default")
      (node (ref "U9") (pin "20") (pinfunction "SCK/CLK_20") (pintype "bidirectional"))
    )
    (net (code "166") (name "unconnected-(U9-SCS{slash}CMD-Pad19)") (class "Default")
      (node (ref "U9") (pin "19") (pinfunction "SCS/CMD_19") (pintype "bidirectional"))
    )
    (net (code "167") (name "unconnected-(U9-SDI{slash}SD1-Pad22)") (class "Default")
      (node (ref "U9") (pin "22") (pinfunction "SDI/SD1_22") (pintype "bidirectional"))
    )
    (net (code "168") (name "unconnected-(U9-SDO{slash}SD0-Pad21)") (class "Default")
      (node (ref "U9") (pin "21") (pinfunction "SDO/SD0_21") (pintype "bidirectional"))
    )
    (net (code "169") (name "unconnected-(U9-SENSOR_VN-Pad5)") (class "Default")
      (node (ref "U9") (pin "5") (pinfunction "SENSOR_VN_5") (pintype "input"))
    )
    (net (code "170") (name "unconnected-(U9-SENSOR_VP-Pad4)") (class "Default")
      (node (ref "U9") (pin "4") (pinfunction "SENSOR_VP_4") (pintype "input"))
    )
    (net (code "171") (name "unconnected-(U9-SHD{slash}SD2-Pad17)") (class "Default")
      (node (ref "U9") (pin "17") (pinfunction "SHD/SD2_17") (pintype "bidirectional"))
    )
    (net (code "172") (name "unconnected-(U9-SWP{slash}SD3-Pad18)") (class "Default")
      (node (ref "U9") (pin "18") (pinfunction "SWP/SD3_18") (pintype "bidirectional"))
    )
    (net (code "173") (name "unconnected-(U10-AIN1-Pad5)") (class "Default")
      (node (ref "U10") (pin "5") (pinfunction "AIN1_5") (pintype "input"))
    )
    (net (code "174") (name "unconnected-(U10-AIN2-Pad6)") (class "Default")
      (node (ref "U10") (pin "6") (pinfunction "AIN2_6") (pintype "input"))
    )
    (net (code "175") (name "unconnected-(U10-AIN3-Pad7)") (class "Default")
      (node (ref "U10") (pin "7") (pinfunction "AIN3_7") (pintype "input"))
    )
    (net (code "176") (name "unconnected-(U10-ALERT{slash}RDY-Pad2)") (class "Default")
      (node (ref "U10") (pin "2") (pinfunction "ALERT/RDY_2") (pintype "output"))
    )
    (net (code "177") (name "unconnected-(U12-EXTINT-Pad4)") (class "Default")
      (node (ref "U12") (pin "4") (pinfunction "EXTINT_4") (pintype "input"))
    )
    (net (code "178") (name "unconnected-(U12-LNA_EN-Pad14)") (class "Default")
      (node (ref "U12") (pin "14") (pinfunction "LNA_EN_14") (pintype "output"))
    )
    (net (code "179") (name "unconnected-(U12-RESET_N-Pad8)") (class "Default")
      (node (ref "U12") (pin "8") (pinfunction "RESET_N_8") (pintype "input"))
    )
    (net (code "180") (name "unconnected-(U12-SAFEBOOT_N-Pad1)") (class "Default")
      (node (ref "U12") (pin "1") (pinfunction "SAFEBOOT_N_1") (pintype "input"))
    )
    (net (code "181") (name "unconnected-(U12-SCL{slash}SPI_CLK-Pad19)") (class "Default")
      (node (ref "U12") (pin "19") (pinfunction "SCL/SPI_CLK_19") (pintype "input"))
    )
    (net (code "182") (name "unconnected-(U12-SDA{slash}SPI_CS_N-Pad18)") (class "Default")
      (node (ref "U12") (pin "18") (pinfunction "SDA/SPI_CS_N_18") (pintype "bidirectional"))
    )
    (net (code "183") (name "unconnected-(U12-USB_DM-Pad5)") (class "Default")
      (node (ref "U12") (pin "5") (pinfunction "USB_DM_5") (pintype "bidirectional"))
    )
    (net (code "184") (name "unconnected-(U12-USB_DP-Pad6)") (class "Default")
      (node (ref "U12") (pin "6") (pinfunction "USB_DP_6") (pintype "bidirectional"))
    )
  )
)
